# 15-DDR4_DEVICES.net
KiCad netlist of a schematic drawn in Altium Designer
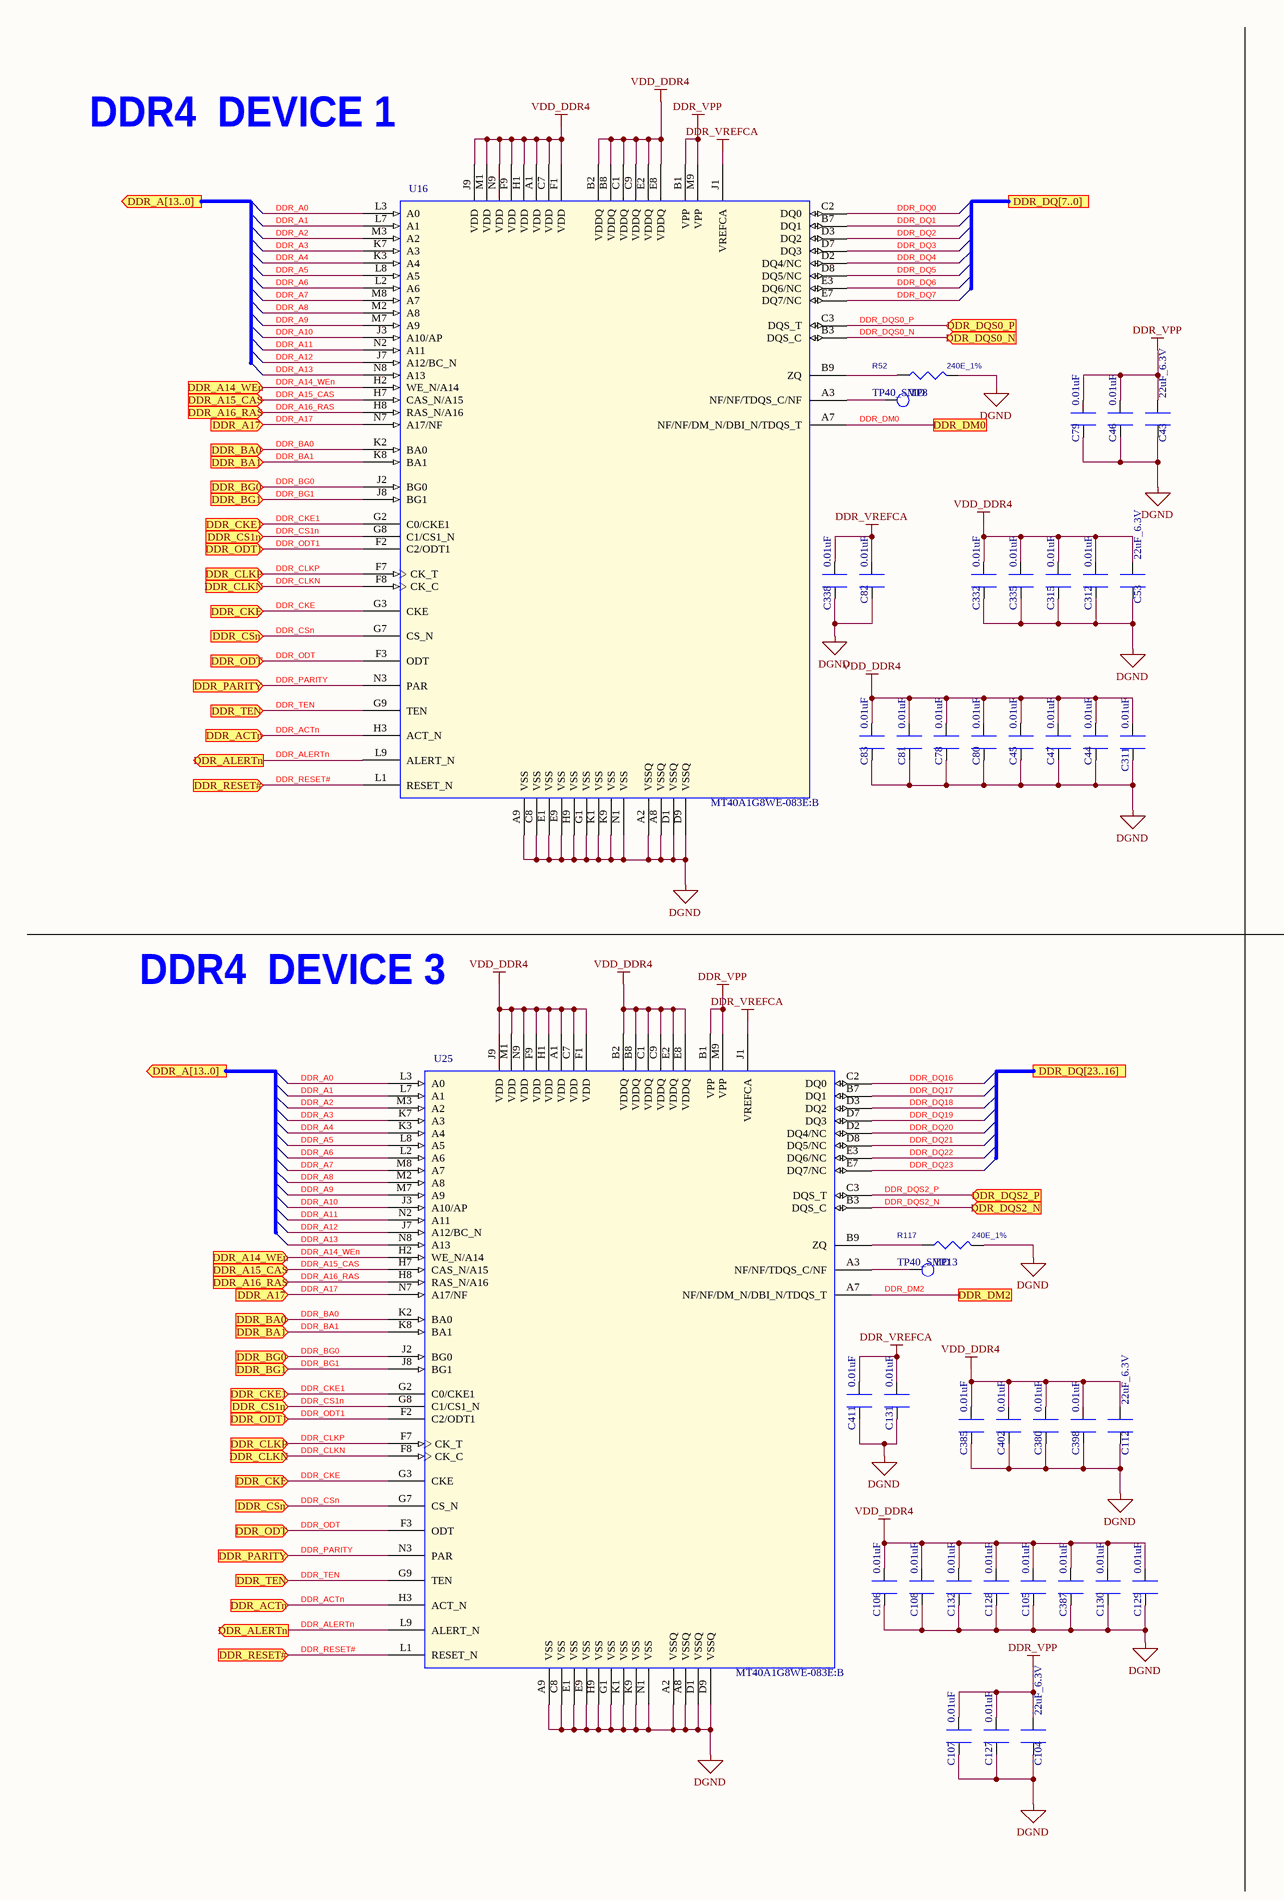
[diagram p0: 15-DDR4 DEVICES.SchDoc, left]
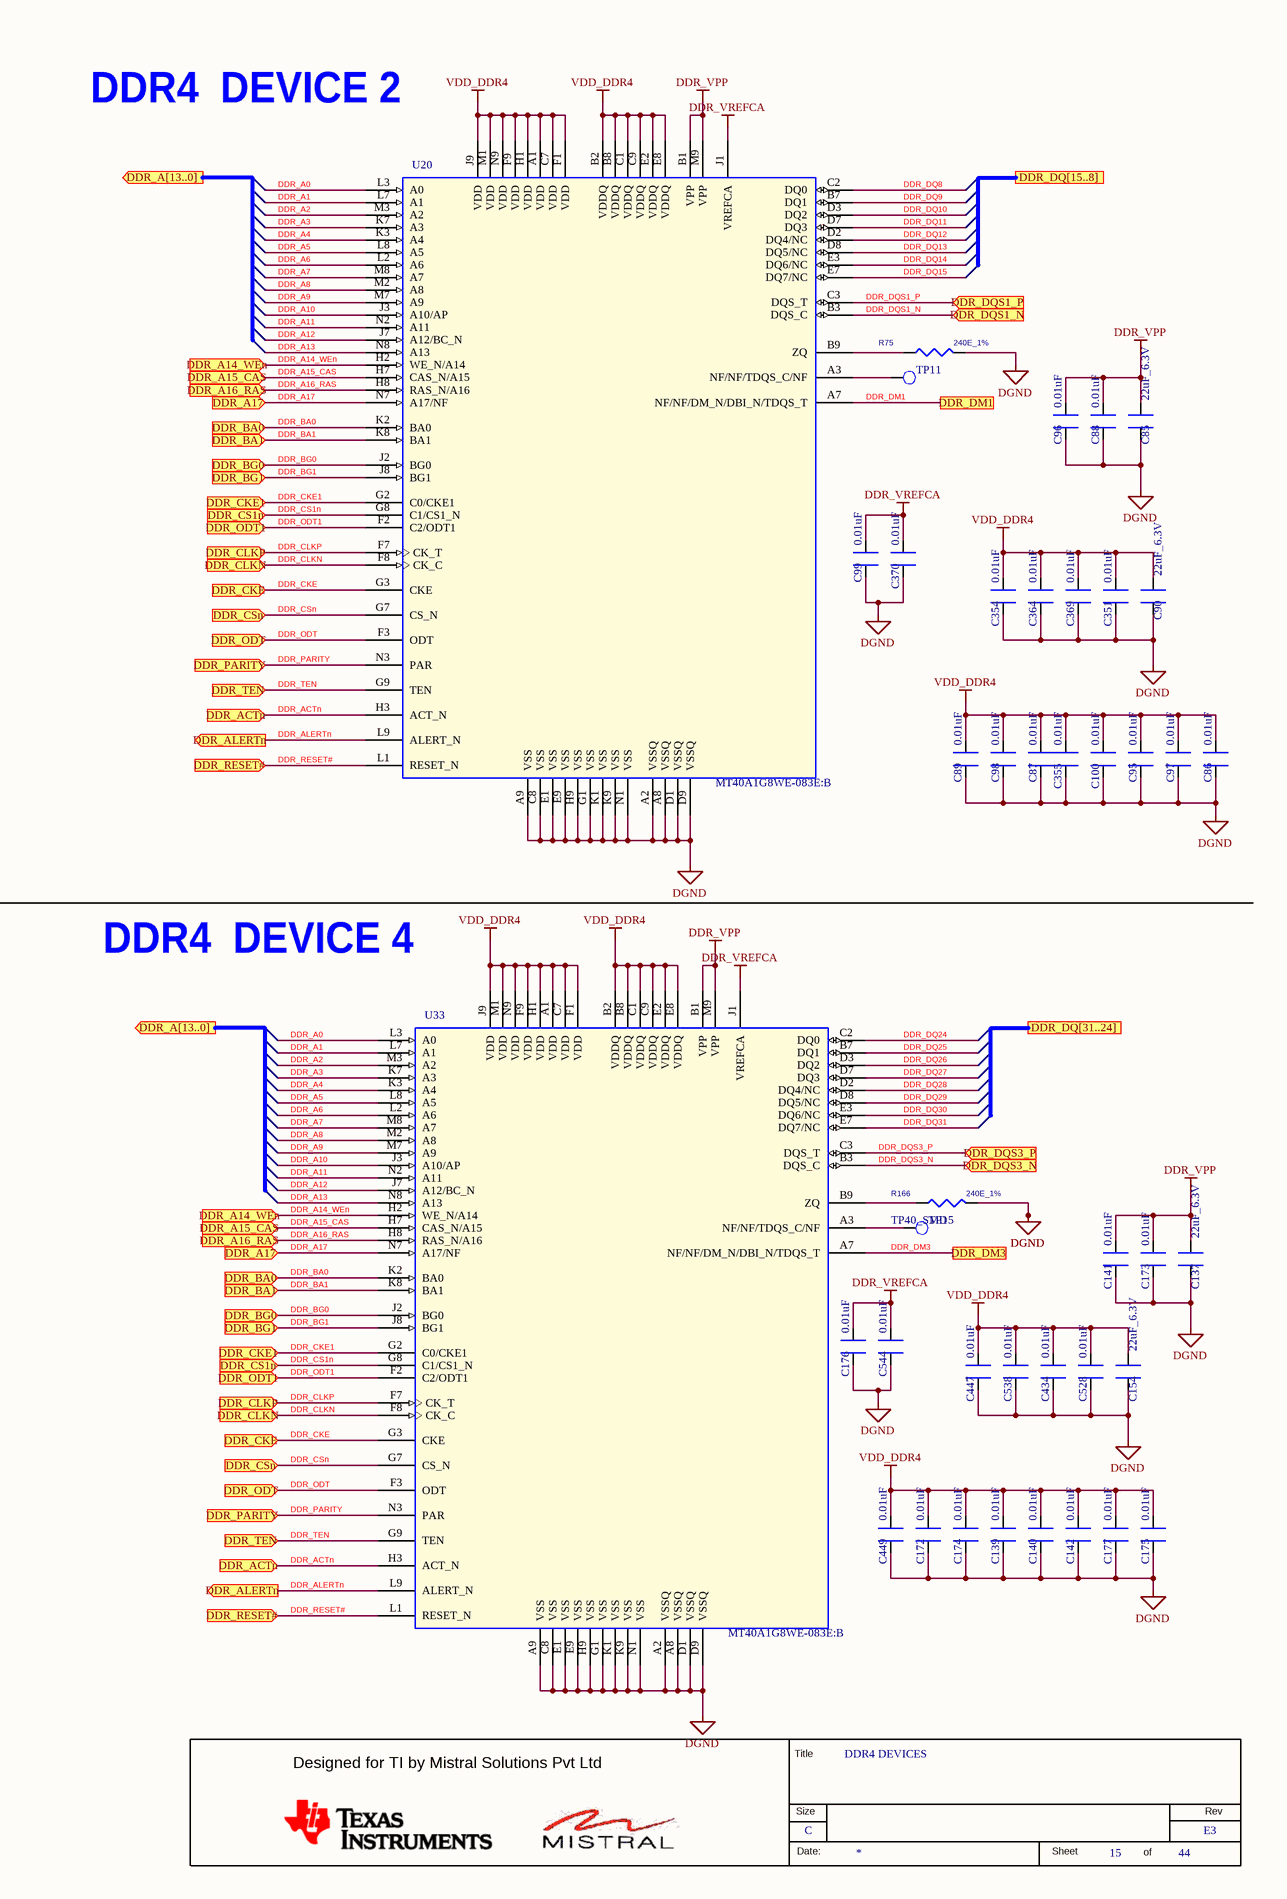
[diagram p1: 15-DDR4 DEVICES.SchDoc, right]

(export (version "E")
  (design (tool "Eeschema 10.0.6"))
  (components
    (comp (ref "C43")
      (value "22uF_6.3V")
      (footprint "TMDX654GPEVM_BRD:CAP0603")
      (description "CAP CERAMIC 22uF 6.3V 20% X5R 0603")
      (fields (field (name "DISTRIBUTOR_PART_NUMBER") "490-7611-2-ND") (field (name "VOLTAGE") "6.3V"))
      (libsource (lib "*") (part "CAP_Dup3"))
    )
    (comp (ref "C44")
      (value "0.01uF")
      (footprint "TMDX654GPEVM_BRD:CAP0201_0-5")
      (description "CAP CERAMIC 0.01uF 25V 10% X5R 0201")
      (fields
        (field (name "MISTRAL PART NO") "120018010007-R")
        (field (name "MFR_PART_NUMBER") "GRM033R61E103KA12J")
      )
      (libsource (lib "*") (part "CAP_Dup3"))
    )
    (comp (ref "C45")
      (value "0.01uF")
      (footprint "TMDX654GPEVM_BRD:CAP0201_0-5")
      (description "CAP CERAMIC 0.01uF 25V 10% X5R 0201")
      (fields
        (field (name "MISTRAL PART NO") "120018010007-R")
        (field (name "MFR_PART_NUMBER") "GRM033R61E103KA12J")
      )
      (libsource (lib "*") (part "CAP_Dup3"))
    )
    (comp (ref "C46")
      (value "0.01uF")
      (footprint "TMDX654GPEVM_BRD:CAP0201_0-5")
      (description "CAP CERAMIC 0.01uF 25V 10% X5R 0201")
      (fields
        (field (name "MISTRAL PART NO") "120018010007-R")
        (field (name "MFR_PART_NUMBER") "GRM033R61E103KA12J")
      )
      (libsource (lib "*") (part "CAP_Dup3"))
    )
    (comp (ref "C47")
      (value "0.01uF")
      (footprint "TMDX654GPEVM_BRD:CAP0201_0-5")
      (description "CAP CERAMIC 0.01uF 25V 10% X5R 0201")
      (fields
        (field (name "MISTRAL PART NO") "120018010007-R")
        (field (name "MFR_PART_NUMBER") "GRM033R61E103KA12J")
      )
      (libsource (lib "*") (part "CAP_Dup3"))
    )
    (comp (ref "C53")
      (value "22uF_6.3V")
      (footprint "TMDX654GPEVM_BRD:CAP0603")
      (description "CAP CERAMIC 22uF 6.3V 20% X5R 0603")
      (fields
        (field (name "MISTRAL PART NO") "120015090007-R")
        (field (name "MFR_PART_NUMBER") "GRM188R60J226MEA0")
      )
      (libsource (lib "*") (part "CAP_Dup3"))
    )
    (comp (ref "C78")
      (value "0.01uF")
      (footprint "TMDX654GPEVM_BRD:CAP0201_0-5")
      (description "CAP CERAMIC 0.01uF 25V 10% X5R 0201")
      (fields
        (field (name "MISTRAL PART NO") "120018010007-R")
        (field (name "MFR_PART_NUMBER") "GRM033R61E103KA12J")
      )
      (libsource (lib "*") (part "CAP_Dup3"))
    )
    (comp (ref "C79")
      (value "0.01uF")
      (footprint "TMDX654GPEVM_BRD:CAP0201_0-5")
      (description "CAP CERAMIC 0.01uF 25V 10% X5R 0201")
      (fields
        (field (name "MISTRAL PART NO") "120018010007-R")
        (field (name "MFR_PART_NUMBER") "GRM033R61E103KA12J")
      )
      (libsource (lib "*") (part "CAP_Dup3"))
    )
    (comp (ref "C80")
      (value "0.01uF")
      (footprint "TMDX654GPEVM_BRD:CAP0201_0-5")
      (description "CAP CERAMIC 0.01uF 25V 10% X5R 0201")
      (fields
        (field (name "MISTRAL PART NO") "120018010007-R")
        (field (name "MFR_PART_NUMBER") "GRM033R61E103KA12J")
      )
      (libsource (lib "*") (part "CAP_Dup3"))
    )
    (comp (ref "C81")
      (value "0.01uF")
      (footprint "TMDX654GPEVM_BRD:CAP0201_0-5")
      (description "CAP CERAMIC 0.01uF 25V 10% X5R 0201")
      (fields
        (field (name "MISTRAL PART NO") "120018010007-R")
        (field (name "MFR_PART_NUMBER") "GRM033R61E103KA12J")
      )
      (libsource (lib "*") (part "CAP_Dup3"))
    )
    (comp (ref "C82")
      (value "0.01uF")
      (footprint "TMDX654GPEVM_BRD:CAP0201_0-5")
      (description "CAP CERAMIC 0.01uF 25V 10% X5R 0201")
      (fields (field (name "DISTRIBUTOR_PART_NUMBER") "GRM033R61E103KA12J-ND") (field (name "VOLTAGE") "25V"))
      (libsource (lib "*") (part "CAP_Dup3"))
    )
    (comp (ref "C83")
      (value "0.01uF")
      (footprint "TMDX654GPEVM_BRD:CAP0201_0-5")
      (description "CAP CERAMIC 0.01uF 25V 10% X5R 0201")
      (fields
        (field (name "MISTRAL PART NO") "120018010007-R")
        (field (name "MFR_PART_NUMBER") "GRM033R61E103KA12J")
      )
      (libsource (lib "*") (part "CAP_Dup3"))
    )
    (comp (ref "C85")
      (value "22uF_6.3V")
      (footprint "TMDX654GPEVM_BRD:CAP0603")
      (description "CAP CERAMIC 22uF 6.3V 20% X5R 0603")
      (fields (field (name "DISTRIBUTOR_PART_NUMBER") "490-7611-2-ND") (field (name "VOLTAGE") "6.3V"))
      (libsource (lib "*") (part "CAP_Dup3"))
    )
    (comp (ref "C86")
      (value "0.01uF")
      (footprint "TMDX654GPEVM_BRD:CAP0201_0-5")
      (description "CAP CERAMIC 0.01uF 25V 10% X5R 0201")
      (fields (field (name "DISTRIBUTOR_PART_NUMBER") "GRM033R61E103KA12J-ND") (field (name "VOLTAGE") "25V"))
      (libsource (lib "*") (part "CAP_Dup3"))
    )
    (comp (ref "C87")
      (value "0.01uF")
      (footprint "TMDX654GPEVM_BRD:CAP0201_0-5")
      (description "CAP CERAMIC 0.01uF 25V 10% X5R 0201")
      (fields
        (field (name "MISTRAL PART NO") "120018010007-R")
        (field (name "MFR_PART_NUMBER") "GRM033R61E103KA12J")
      )
      (libsource (lib "*") (part "CAP_Dup3"))
    )
    (comp (ref "C88")
      (value "0.01uF")
      (footprint "TMDX654GPEVM_BRD:CAP0201_0-5")
      (description "CAP CERAMIC 0.01uF 25V 10% X5R 0201")
      (fields (field (name "DISTRIBUTOR_PART_NUMBER") "GRM033R61E103KA12J-ND") (field (name "VOLTAGE") "25V"))
      (libsource (lib "*") (part "CAP_Dup3"))
    )
    (comp (ref "C89")
      (value "0.01uF")
      (footprint "TMDX654GPEVM_BRD:CAP0201_0-5")
      (description "CAP CERAMIC 0.01uF 25V 10% X5R 0201")
      (fields
        (field (name "MISTRAL PART NO") "120018010007-R")
        (field (name "MFR_PART_NUMBER") "GRM033R61E103KA12J")
      )
      (libsource (lib "*") (part "CAP_Dup3"))
    )
    (comp (ref "C90")
      (value "22uF_6.3V")
      (footprint "TMDX654GPEVM_BRD:CAP0603")
      (description "CAP CERAMIC 22uF 6.3V 20% X5R 0603")
      (fields (field (name "DISTRIBUTOR_PART_NUMBER") "490-7611-2-ND") (field (name "VOLTAGE") "6.3V"))
      (libsource (lib "*") (part "CAP_Dup3"))
    )
    (comp (ref "C95")
      (value "0.01uF")
      (footprint "TMDX654GPEVM_BRD:CAP0201_0-5")
      (description "CAP CERAMIC 0.01uF 25V 10% X5R 0201")
      (fields
        (field (name "MISTRAL PART NO") "120018010007-R")
        (field (name "MFR_PART_NUMBER") "GRM033R61E103KA12J")
      )
      (libsource (lib "*") (part "CAP_Dup3"))
    )
    (comp (ref "C96")
      (value "0.01uF")
      (footprint "TMDX654GPEVM_BRD:CAP0201_0-5")
      (description "CAP CERAMIC 0.01uF 25V 10% X5R 0201")
      (fields (field (name "DISTRIBUTOR_PART_NUMBER") "GRM033R61E103KA12J-ND") (field (name "VOLTAGE") "25V"))
      (libsource (lib "*") (part "CAP_Dup3"))
    )
    (comp (ref "C97")
      (value "0.01uF")
      (footprint "TMDX654GPEVM_BRD:CAP0201_0-5")
      (description "CAP CERAMIC 0.01uF 25V 10% X5R 0201")
      (fields
        (field (name "MISTRAL PART NO") "120018010007-R")
        (field (name "MFR_PART_NUMBER") "GRM033R61E103KA12J")
      )
      (libsource (lib "*") (part "CAP_Dup3"))
    )
    (comp (ref "C98")
      (value "0.01uF")
      (footprint "TMDX654GPEVM_BRD:CAP0201_0-5")
      (description "CAP CERAMIC 0.01uF 25V 10% X5R 0201")
      (fields
        (field (name "MISTRAL PART NO") "120018010007-R")
        (field (name "MFR_PART_NUMBER") "GRM033R61E103KA12J")
      )
      (libsource (lib "*") (part "CAP_Dup3"))
    )
    (comp (ref "C99")
      (value "0.01uF")
      (footprint "TMDX654GPEVM_BRD:CAP0201_0-5")
      (description "CAP CERAMIC 0.01uF 25V 10% X5R 0201")
      (fields (field (name "DISTRIBUTOR_PART_NUMBER") "GRM033R61E103KA12J-ND") (field (name "VOLTAGE") "25V"))
      (libsource (lib "*") (part "CAP_Dup3"))
    )
    (comp (ref "C100")
      (value "0.01uF")
      (footprint "TMDX654GPEVM_BRD:CAP0201_0-5")
      (description "CAP CERAMIC 0.01uF 25V 10% X5R 0201")
      (fields
        (field (name "MISTRAL PART NO") "120018010007-R")
        (field (name "MFR_PART_NUMBER") "GRM033R61E103KA12J")
      )
      (libsource (lib "*") (part "CAP_Dup3"))
    )
    (comp (ref "C104")
      (value "22uF_6.3V")
      (footprint "TMDX654GPEVM_BRD:CAP0603")
      (description "CAP CERAMIC 22uF 6.3V 20% X5R 0603")
      (fields
        (field (name "MISTRAL PART NO") "120015090007-R")
        (field (name "MFR_PART_NUMBER") "GRM188R60J226MEA0")
      )
      (libsource (lib "*") (part "CAP_Dup3"))
    )
    (comp (ref "C105")
      (value "0.01uF")
      (footprint "TMDX654GPEVM_BRD:CAP0201_0-5")
      (description "CAP CERAMIC 0.01uF 25V 10% X5R 0201")
      (fields
        (field (name "MISTRAL PART NO") "120018010007-R")
        (field (name "MFR_PART_NUMBER") "GRM033R61E103KA12J")
      )
      (libsource (lib "*") (part "CAP_Dup3"))
    )
    (comp (ref "C106")
      (value "0.01uF")
      (footprint "TMDX654GPEVM_BRD:CAP0201_0-5")
      (description "CAP CERAMIC 0.01uF 25V 10% X5R 0201")
      (fields
        (field (name "MISTRAL PART NO") "120018010007-R")
        (field (name "MFR_PART_NUMBER") "GRM033R61E103KA12J")
      )
      (libsource (lib "*") (part "CAP_Dup3"))
    )
    (comp (ref "C107")
      (value "0.01uF")
      (footprint "TMDX654GPEVM_BRD:CAP0201_0-5")
      (description "CAP CERAMIC 0.01uF 25V 10% X5R 0201")
      (fields (field (name "DISTRIBUTOR_PART_NUMBER") "GRM033R61E103KA12J-ND") (field (name "VOLTAGE") "25V"))
      (libsource (lib "*") (part "CAP_Dup3"))
    )
    (comp (ref "C108")
      (value "0.01uF")
      (footprint "TMDX654GPEVM_BRD:CAP0201_0-5")
      (description "CAP CERAMIC 0.01uF 25V 10% X5R 0201")
      (fields
        (field (name "MISTRAL PART NO") "120018010007-R")
        (field (name "MFR_PART_NUMBER") "GRM033R61E103KA12J")
      )
      (libsource (lib "*") (part "CAP_Dup3"))
    )
    (comp (ref "C112")
      (value "22uF_6.3V")
      (footprint "TMDX654GPEVM_BRD:CAP0603")
      (description "CAP CERAMIC 22uF 6.3V 20% X5R 0603")
      (fields (field (name "DISTRIBUTOR_PART_NUMBER") "490-7611-2-ND") (field (name "VOLTAGE") "6.3V"))
      (libsource (lib "*") (part "CAP_Dup3"))
    )
    (comp (ref "C127")
      (value "0.01uF")
      (footprint "TMDX654GPEVM_BRD:CAP0201_0-5")
      (description "CAP CERAMIC 0.01uF 25V 10% X5R 0201")
      (fields (field (name "DISTRIBUTOR_PART_NUMBER") "GRM033R61E103KA12J-ND") (field (name "VOLTAGE") "25V"))
      (libsource (lib "*") (part "CAP_Dup3"))
    )
    (comp (ref "C128")
      (value "0.01uF")
      (footprint "TMDX654GPEVM_BRD:CAP0201_0-5")
      (description "CAP CERAMIC 0.01uF 25V 10% X5R 0201")
      (fields
        (field (name "MISTRAL PART NO") "120018010007-R")
        (field (name "MFR_PART_NUMBER") "GRM033R61E103KA12J")
      )
      (libsource (lib "*") (part "CAP_Dup3"))
    )
    (comp (ref "C129")
      (value "0.01uF")
      (footprint "TMDX654GPEVM_BRD:CAP0201_0-5")
      (description "CAP CERAMIC 0.01uF 25V 10% X5R 0201")
      (fields (field (name "DISTRIBUTOR_PART_NUMBER") "GRM033R61E103KA12J-ND") (field (name "VOLTAGE") "25V"))
      (libsource (lib "*") (part "CAP_Dup3"))
    )
    (comp (ref "C130")
      (value "0.01uF")
      (footprint "TMDX654GPEVM_BRD:CAP0201_0-5")
      (description "CAP CERAMIC 0.01uF 25V 10% X5R 0201")
      (fields
        (field (name "MISTRAL PART NO") "120018010007-R")
        (field (name "MFR_PART_NUMBER") "GRM033R61E103KA12J")
      )
      (libsource (lib "*") (part "CAP_Dup3"))
    )
    (comp (ref "C131")
      (value "0.01uF")
      (footprint "TMDX654GPEVM_BRD:CAP0201_0-5")
      (description "CAP CERAMIC 0.01uF 25V 10% X5R 0201")
      (fields (field (name "DISTRIBUTOR_PART_NUMBER") "GRM033R61E103KA12J-ND") (field (name "VOLTAGE") "25V"))
      (libsource (lib "*") (part "CAP_Dup3"))
    )
    (comp (ref "C132")
      (value "0.01uF")
      (footprint "TMDX654GPEVM_BRD:CAP0201_0-5")
      (description "CAP CERAMIC 0.01uF 25V 10% X5R 0201")
      (fields
        (field (name "MISTRAL PART NO") "120018010007-R")
        (field (name "MFR_PART_NUMBER") "GRM033R61E103KA12J")
      )
      (libsource (lib "*") (part "CAP_Dup3"))
    )
    (comp (ref "C137")
      (value "22uF_6.3V")
      (footprint "TMDX654GPEVM_BRD:CAP0603")
      (description "CAP CERAMIC 22uF 6.3V 20% X5R 0603")
      (fields
        (field (name "MISTRAL PART NO") "120015090007-R")
        (field (name "MFR_PART_NUMBER") "GRM188R60J226MEA0")
      )
      (libsource (lib "*") (part "CAP_Dup3"))
    )
    (comp (ref "C139")
      (value "0.01uF")
      (footprint "TMDX654GPEVM_BRD:CAP0201_0-5")
      (description "CAP CERAMIC 0.01uF 25V 10% X5R 0201")
      (fields
        (field (name "MISTRAL PART NO") "120018010007-R")
        (field (name "MFR_PART_NUMBER") "GRM033R61E103KA12J")
      )
      (libsource (lib "*") (part "CAP_Dup3"))
    )
    (comp (ref "C140")
      (value "0.01uF")
      (footprint "TMDX654GPEVM_BRD:CAP0201_0-5")
      (description "CAP CERAMIC 0.01uF 25V 10% X5R 0201")
      (fields
        (field (name "MISTRAL PART NO") "120018010007-R")
        (field (name "MFR_PART_NUMBER") "GRM033R61E103KA12J")
      )
      (libsource (lib "*") (part "CAP_Dup3"))
    )
    (comp (ref "C141")
      (value "0.01uF")
      (footprint "TMDX654GPEVM_BRD:CAP0201_0-5")
      (description "CAP CERAMIC 0.01uF 25V 10% X5R 0201")
      (fields (field (name "DISTRIBUTOR_PART_NUMBER") "GRM033R61E103KA12J-ND") (field (name "VOLTAGE") "25V"))
      (libsource (lib "*") (part "CAP_Dup3"))
    )
    (comp (ref "C142")
      (value "0.01uF")
      (footprint "TMDX654GPEVM_BRD:CAP0201_0-5")
      (description "CAP CERAMIC 0.01uF 25V 10% X5R 0201")
      (fields
        (field (name "MISTRAL PART NO") "120018010007-R")
        (field (name "MFR_PART_NUMBER") "GRM033R61E103KA12J")
      )
      (libsource (lib "*") (part "CAP_Dup3"))
    )
    (comp (ref "C154")
      (value "22uF_6.3V")
      (footprint "TMDX654GPEVM_BRD:CAP0603")
      (description "CAP CERAMIC 22uF 6.3V 20% X5R 0603")
      (fields (field (name "DISTRIBUTOR_PART_NUMBER") "490-7611-2-ND") (field (name "VOLTAGE") "6.3V"))
      (libsource (lib "*") (part "CAP_Dup3"))
    )
    (comp (ref "C172")
      (value "0.01uF")
      (footprint "TMDX654GPEVM_BRD:CAP0201_0-5")
      (description "CAP CERAMIC 0.01uF 25V 10% X5R 0201")
      (fields
        (field (name "MISTRAL PART NO") "120018010007-R")
        (field (name "MFR_PART_NUMBER") "GRM033R61E103KA12J")
      )
      (libsource (lib "*") (part "CAP_Dup3"))
    )
    (comp (ref "C173")
      (value "0.01uF")
      (footprint "TMDX654GPEVM_BRD:CAP0201_0-5")
      (description "CAP CERAMIC 0.01uF 25V 10% X5R 0201")
      (fields (field (name "DISTRIBUTOR_PART_NUMBER") "GRM033R61E103KA12J-ND") (field (name "VOLTAGE") "25V"))
      (libsource (lib "*") (part "CAP_Dup3"))
    )
    (comp (ref "C174")
      (value "0.01uF")
      (footprint "TMDX654GPEVM_BRD:CAP0201_0-5")
      (description "CAP CERAMIC 0.01uF 25V 10% X5R 0201")
      (fields
        (field (name "MISTRAL PART NO") "120018010007-R")
        (field (name "MFR_PART_NUMBER") "GRM033R61E103KA12J")
      )
      (libsource (lib "*") (part "CAP_Dup3"))
    )
    (comp (ref "C175")
      (value "0.01uF")
      (footprint "TMDX654GPEVM_BRD:CAP0201_0-5")
      (description "CAP CERAMIC 0.01uF 25V 10% X5R 0201")
      (fields (field (name "DISTRIBUTOR_PART_NUMBER") "GRM033R61E103KA12J-ND") (field (name "VOLTAGE") "25V"))
      (libsource (lib "*") (part "CAP_Dup3"))
    )
    (comp (ref "C176")
      (value "0.01uF")
      (footprint "TMDX654GPEVM_BRD:CAP0201_0-5")
      (description "CAP CERAMIC 0.01uF 25V 10% X5R 0201")
      (fields (field (name "DISTRIBUTOR_PART_NUMBER") "GRM033R61E103KA12J-ND") (field (name "VOLTAGE") "25V"))
      (libsource (lib "*") (part "CAP_Dup3"))
    )
    (comp (ref "C177")
      (value "0.01uF")
      (footprint "TMDX654GPEVM_BRD:CAP0201_0-5")
      (description "CAP CERAMIC 0.01uF 25V 10% X5R 0201")
      (fields
        (field (name "MISTRAL PART NO") "120018010007-R")
        (field (name "MFR_PART_NUMBER") "GRM033R61E103KA12J")
      )
      (libsource (lib "*") (part "CAP_Dup3"))
    )
    (comp (ref "C311")
      (value "0.01uF")
      (footprint "TMDX654GPEVM_BRD:CAP0201_0-5")
      (description "CAP CERAMIC 0.01uF 25V 10% X5R 0201")
      (fields
        (field (name "MISTRAL PART NO") "120018010007-R")
        (field (name "MFR_PART_NUMBER") "GRM033R61E103KA12J")
      )
      (libsource (lib "*") (part "CAP_Dup3"))
    )
    (comp (ref "C312")
      (value "0.01uF")
      (footprint "TMDX654GPEVM_BRD:CAP0201_0-5")
      (description "CAP CERAMIC 0.01uF 25V 10% X5R 0201")
      (fields (field (name "DISTRIBUTOR_PART_NUMBER") "GRM033R61E103KA12J-ND") (field (name "VOLTAGE") "25V"))
      (libsource (lib "*") (part "CAP_Dup3"))
    )
    (comp (ref "C315")
      (value "0.01uF")
      (footprint "TMDX654GPEVM_BRD:CAP0201_0-5")
      (description "CAP CERAMIC 0.01uF 25V 10% X5R 0201")
      (fields (field (name "DISTRIBUTOR_PART_NUMBER") "GRM033R61E103KA12J-ND") (field (name "VOLTAGE") "25V"))
      (libsource (lib "*") (part "CAP_Dup3"))
    )
    (comp (ref "C332")
      (value "0.01uF")
      (footprint "TMDX654GPEVM_BRD:CAP0201_0-5")
      (description "CAP CERAMIC 0.01uF 25V 10% X5R 0201")
      (fields (field (name "DISTRIBUTOR_PART_NUMBER") "GRM033R61E103KA12J-ND") (field (name "VOLTAGE") "25V"))
      (libsource (lib "*") (part "CAP_Dup3"))
    )
    (comp (ref "C335")
      (value "0.01uF")
      (footprint "TMDX654GPEVM_BRD:CAP0201_0-5")
      (description "CAP CERAMIC 0.01uF 25V 10% X5R 0201")
      (fields (field (name "DISTRIBUTOR_PART_NUMBER") "GRM033R61E103KA12J-ND") (field (name "VOLTAGE") "25V"))
      (libsource (lib "*") (part "CAP_Dup3"))
    )
    (comp (ref "C338")
      (value "0.01uF")
      (footprint "TMDX654GPEVM_BRD:CAP0201_0-5")
      (description "CAP CERAMIC 0.01uF 25V 10% X5R 0201")
      (fields (field (name "DISTRIBUTOR_PART_NUMBER") "GRM033R61E103KA12J-ND") (field (name "VOLTAGE") "25V"))
      (libsource (lib "*") (part "CAP_Dup3"))
    )
    (comp (ref "C351")
      (value "0.01uF")
      (footprint "TMDX654GPEVM_BRD:CAP0201_0-5")
      (description "CAP CERAMIC 0.01uF 25V 10% X5R 0201")
      (fields
        (field (name "MISTRAL PART NO") "120018010007-R")
        (field (name "MFR_PART_NUMBER") "GRM033R61E103KA12J")
      )
      (libsource (lib "*") (part "CAP_Dup3"))
    )
    (comp (ref "C354")
      (value "0.01uF")
      (footprint "TMDX654GPEVM_BRD:CAP0201_0-5")
      (description "CAP CERAMIC 0.01uF 25V 10% X5R 0201")
      (fields
        (field (name "MISTRAL PART NO") "120018010007-R")
        (field (name "MFR_PART_NUMBER") "GRM033R61E103KA12J")
      )
      (libsource (lib "*") (part "CAP_Dup3"))
    )
    (comp (ref "C355")
      (value "0.01uF")
      (footprint "TMDX654GPEVM_BRD:CAP0201_0-5")
      (description "CAP CERAMIC 0.01uF 25V 10% X5R 0201")
      (fields
        (field (name "MISTRAL PART NO") "120018010007-R")
        (field (name "MFR_PART_NUMBER") "GRM033R61E103KA12J")
      )
      (libsource (lib "*") (part "CAP_Dup3"))
    )
    (comp (ref "C364")
      (value "0.01uF")
      (footprint "TMDX654GPEVM_BRD:CAP0201_0-5")
      (description "CAP CERAMIC 0.01uF 25V 10% X5R 0201")
      (fields
        (field (name "MISTRAL PART NO") "120018010007-R")
        (field (name "MFR_PART_NUMBER") "GRM033R61E103KA12J")
      )
      (libsource (lib "*") (part "CAP_Dup3"))
    )
    (comp (ref "C369")
      (value "0.01uF")
      (footprint "TMDX654GPEVM_BRD:CAP0201_0-5")
      (description "CAP CERAMIC 0.01uF 25V 10% X5R 0201")
      (fields
        (field (name "MISTRAL PART NO") "120018010007-R")
        (field (name "MFR_PART_NUMBER") "GRM033R61E103KA12J")
      )
      (libsource (lib "*") (part "CAP_Dup3"))
    )
    (comp (ref "C370")
      (value "0.01uF")
      (footprint "TMDX654GPEVM_BRD:CAP0201_0-5")
      (description "CAP CERAMIC 0.01uF 25V 10% X5R 0201")
      (fields (field (name "DISTRIBUTOR_PART_NUMBER") "GRM033R61E103KA12J-ND") (field (name "VOLTAGE") "25V"))
      (libsource (lib "*") (part "CAP_Dup3"))
    )
    (comp (ref "C380")
      (value "0.01uF")
      (footprint "TMDX654GPEVM_BRD:CAP0201_0-5")
      (description "CAP CERAMIC 0.01uF 25V 10% X5R 0201")
      (fields
        (field (name "MISTRAL PART NO") "120018010007-R")
        (field (name "MFR_PART_NUMBER") "GRM033R61E103KA12J")
      )
      (libsource (lib "*") (part "CAP_Dup3"))
    )
    (comp (ref "C385")
      (value "0.01uF")
      (footprint "TMDX654GPEVM_BRD:CAP0201_0-5")
      (description "CAP CERAMIC 0.01uF 25V 10% X5R 0201")
      (fields
        (field (name "MISTRAL PART NO") "120018010007-R")
        (field (name "MFR_PART_NUMBER") "GRM033R61E103KA12J")
      )
      (libsource (lib "*") (part "CAP_Dup3"))
    )
    (comp (ref "C387")
      (value "0.01uF")
      (footprint "TMDX654GPEVM_BRD:CAP0201_0-5")
      (description "CAP CERAMIC 0.01uF 25V 10% X5R 0201")
      (fields
        (field (name "MISTRAL PART NO") "120018010007-R")
        (field (name "MFR_PART_NUMBER") "GRM033R61E103KA12J")
      )
      (libsource (lib "*") (part "CAP_Dup3"))
    )
    (comp (ref "C398")
      (value "0.01uF")
      (footprint "TMDX654GPEVM_BRD:CAP0201_0-5")
      (description "CAP CERAMIC 0.01uF 25V 10% X5R 0201")
      (fields
        (field (name "MISTRAL PART NO") "120018010007-R")
        (field (name "MFR_PART_NUMBER") "GRM033R61E103KA12J")
      )
      (libsource (lib "*") (part "CAP_Dup3"))
    )
    (comp (ref "C402")
      (value "0.01uF")
      (footprint "TMDX654GPEVM_BRD:CAP0201_0-5")
      (description "CAP CERAMIC 0.01uF 25V 10% X5R 0201")
      (fields
        (field (name "MISTRAL PART NO") "120018010007-R")
        (field (name "MFR_PART_NUMBER") "GRM033R61E103KA12J")
      )
      (libsource (lib "*") (part "CAP_Dup3"))
    )
    (comp (ref "C411")
      (value "0.01uF")
      (footprint "TMDX654GPEVM_BRD:CAP0201_0-5")
      (description "CAP CERAMIC 0.01uF 25V 10% X5R 0201")
      (fields (field (name "DISTRIBUTOR_PART_NUMBER") "GRM033R61E103KA12J-ND") (field (name "VOLTAGE") "25V"))
      (libsource (lib "*") (part "CAP_Dup3"))
    )
    (comp (ref "C434")
      (value "0.01uF")
      (footprint "TMDX654GPEVM_BRD:CAP0201_0-5")
      (description "CAP CERAMIC 0.01uF 25V 10% X5R 0201")
      (fields
        (field (name "MISTRAL PART NO") "120018010007-R")
        (field (name "MFR_PART_NUMBER") "GRM033R61E103KA12J")
      )
      (libsource (lib "*") (part "CAP_Dup3"))
    )
    (comp (ref "C447")
      (value "0.01uF")
      (footprint "TMDX654GPEVM_BRD:CAP0201_0-5")
      (description "CAP CERAMIC 0.01uF 25V 10% X5R 0201")
      (fields
        (field (name "MISTRAL PART NO") "120018010007-R")
        (field (name "MFR_PART_NUMBER") "GRM033R61E103KA12J")
      )
      (libsource (lib "*") (part "CAP_Dup3"))
    )
    (comp (ref "C449")
      (value "0.01uF")
      (footprint "TMDX654GPEVM_BRD:CAP0201_0-5")
      (description "CAP CERAMIC 0.01uF 25V 10% X5R 0201")
      (fields
        (field (name "MISTRAL PART NO") "120018010007-R")
        (field (name "MFR_PART_NUMBER") "GRM033R61E103KA12J")
      )
      (libsource (lib "*") (part "CAP_Dup3"))
    )
    (comp (ref "C528")
      (value "0.01uF")
      (footprint "TMDX654GPEVM_BRD:CAP0201_0-5")
      (description "CAP CERAMIC 0.01uF 25V 10% X5R 0201")
      (fields
        (field (name "MISTRAL PART NO") "120018010007-R")
        (field (name "MFR_PART_NUMBER") "GRM033R61E103KA12J")
      )
      (libsource (lib "*") (part "CAP_Dup3"))
    )
    (comp (ref "C538")
      (value "0.01uF")
      (footprint "TMDX654GPEVM_BRD:CAP0201_0-5")
      (description "CAP CERAMIC 0.01uF 25V 10% X5R 0201")
      (fields
        (field (name "MISTRAL PART NO") "120018010007-R")
        (field (name "MFR_PART_NUMBER") "GRM033R61E103KA12J")
      )
      (libsource (lib "*") (part "CAP_Dup3"))
    )
    (comp (ref "C544")
      (value "0.01uF")
      (footprint "TMDX654GPEVM_BRD:CAP0201_0-5")
      (description "CAP CERAMIC 0.01uF 25V 10% X5R 0201")
      (fields (field (name "DISTRIBUTOR_PART_NUMBER") "GRM033R61E103KA12J-ND") (field (name "VOLTAGE") "25V"))
      (libsource (lib "*") (part "CAP_Dup3"))
    )
    (comp (ref "R52")
      (value "240E_1%")
      (footprint "RES0402")
      (description "RES 240E 1/10W 1% 0402")
      (fields (field (name "DISTRIBUTOR_PART_NUMBER") "P240LCT-ND") (field (name "VOLTAGE") "NA"))
      (libsource (lib "*") (part "RESISTOR_Dup1"))
    )
    (comp (ref "R75")
      (value "240E_1%")
      (footprint "RES0402")
      (description "RES 240E 1/10W 1% 0402")
      (fields (field (name "DISTRIBUTOR_PART_NUMBER") "P240LCT-ND") (field (name "VOLTAGE") "NA"))
      (libsource (lib "*") (part "RESISTOR_Dup1"))
    )
    (comp (ref "R117")
      (value "240E_1%")
      (footprint "RES0402")
      (description "RES 240E 1/10W 1% 0402")
      (fields
        (field (name "MISTRAL PART NO") "110011060017-R")
        (field (name "MFR_PART_NUMBER") "ERJ-2RKF2400X")
      )
      (libsource (lib "*") (part "RESISTOR_Dup1"))
    )
    (comp (ref "R166")
      (value "240E_1%")
      (footprint "RES0402")
      (description "RES 240E 1/10W 1% 0402")
      (fields
        (field (name "MISTRAL PART NO") "110011060017-R")
        (field (name "MFR_PART_NUMBER") "ERJ-2RKF2400X")
      )
      (libsource (lib "*") (part "RESISTOR_Dup1"))
    )
    (comp (ref "TP8")
      (value "TP40_SMD")
      (footprint "TP40_SMD")
      (description "TESTPOINT CIR 40 SMD")
      (fields (field (name "VOLTAGE") "NA") (field (name "MISTRAL PART NO") "130009030933"))
      (libsource (lib "*") (part "TESTPOINT"))
    )
    (comp (ref "TP11")
      (value "TP40_SMD")
      (footprint "TP40_SMD")
      (description "TESTPOINT CIR 40 SMD")
      (fields (field (name "DISTRIBUTOR_PART_NUMBER") "NA") (field (name "MISTRAL PART NO") "130009030933"))
      (libsource (lib "*") (part "TESTPOINT"))
    )
    (comp (ref "TP13")
      (value "TP40_SMD")
      (footprint "TP40_SMD")
      (description "TESTPOINT CIR 40 SMD")
      (fields (field (name "VOLTAGE") "NA") (field (name "MISTRAL PART NO") "130009030933"))
      (libsource (lib "*") (part "TESTPOINT"))
    )
    (comp (ref "TP15")
      (value "TP40_SMD")
      (footprint "TP40_SMD")
      (description "TESTPOINT CIR 40 SMD")
      (fields (field (name "VOLTAGE") "NA") (field (name "MISTRAL PART NO") "130009030933"))
      (libsource (lib "*") (part "TESTPOINT"))
    )
    (comp (ref "U16")
      (value "MT40A1G8WE-083E:B")
      (footprint "FBGA78_31-49_320X480_1-2")
      (description "IC 1G8 DDR4 SDRAM MEMORY FBGA78")
      (fields (field (name "DISTRIBUTOR_PART_NUMBER") "557-1727-1-ND") (field (name "VOLTAGE") "NA"))
      (libsource (lib "*") (part "MT40A1G8WE-083_FBGA78"))
    )
    (comp (ref "U20")
      (value "MT40A1G8WE-083E:B")
      (footprint "FBGA78_31-49_320X480_1-2")
      (description "IC 1G8 DDR4 SDRAM MEMORY FBGA78")
      (fields (field (name "DISTRIBUTOR_PART_NUMBER") "557-1727-1-ND") (field (name "VOLTAGE") "NA"))
      (libsource (lib "*") (part "MT40A1G8WE-083_FBGA78"))
    )
    (comp (ref "U25")
      (value "MT40A1G8WE-083E:B")
      (footprint "FBGA78_31-49_320X480_1-2")
      (description "IC 1G8 DDR4 SDRAM MEMORY FBGA78")
      (fields (field (name "MISTRAL PART NO") "141117080006-R") (field (name "TOLERANCE") "NA"))
      (libsource (lib "*") (part "MT40A1G8WE-083_FBGA78"))
    )
    (comp (ref "U33")
      (value "MT40A1G8WE-083E:B")
      (footprint "FBGA78_31-49_320X480_1-2")
      (description "IC 1G8 DDR4 SDRAM MEMORY FBGA78")
      (fields (field (name "MISTRAL PART NO") "141117080006-R") (field (name "TOLERANCE") "NA"))
      (libsource (lib "*") (part "MT40A1G8WE-083_FBGA78"))
    )
  )
  (nets
    (net (code "1") (name "/DDR_A0") (class "Default")
      (node (ref "U16") (pin "L3") (pinfunction "A0_L3") (pintype "input"))
      (node (ref "U20") (pin "L3") (pinfunction "A0_L3") (pintype "input"))
      (node (ref "U25") (pin "L3") (pinfunction "A0_L3") (pintype "input"))
      (node (ref "U33") (pin "L3") (pinfunction "A0_L3") (pintype "input"))
    )
    (net (code "2") (name "/DDR_A1") (class "Default")
      (node (ref "U16") (pin "L7") (pinfunction "A1_L7") (pintype "input"))
      (node (ref "U20") (pin "L7") (pinfunction "A1_L7") (pintype "input"))
      (node (ref "U25") (pin "L7") (pinfunction "A1_L7") (pintype "input"))
      (node (ref "U33") (pin "L7") (pinfunction "A1_L7") (pintype "input"))
    )
    (net (code "3") (name "/DDR_A2") (class "Default")
      (node (ref "U16") (pin "M3") (pinfunction "A2_M3") (pintype "input"))
      (node (ref "U20") (pin "M3") (pinfunction "A2_M3") (pintype "input"))
      (node (ref "U25") (pin "M3") (pinfunction "A2_M3") (pintype "input"))
      (node (ref "U33") (pin "M3") (pinfunction "A2_M3") (pintype "input"))
    )
    (net (code "4") (name "/DDR_A3") (class "Default")
      (node (ref "U16") (pin "K7") (pinfunction "A3_K7") (pintype "input"))
      (node (ref "U20") (pin "K7") (pinfunction "A3_K7") (pintype "input"))
      (node (ref "U25") (pin "K7") (pinfunction "A3_K7") (pintype "input"))
      (node (ref "U33") (pin "K7") (pinfunction "A3_K7") (pintype "input"))
    )
    (net (code "5") (name "/DDR_A4") (class "Default")
      (node (ref "U16") (pin "K3") (pinfunction "A4_K3") (pintype "input"))
      (node (ref "U20") (pin "K3") (pinfunction "A4_K3") (pintype "input"))
      (node (ref "U25") (pin "K3") (pinfunction "A4_K3") (pintype "input"))
      (node (ref "U33") (pin "K3") (pinfunction "A4_K3") (pintype "input"))
    )
    (net (code "6") (name "/DDR_A5") (class "Default")
      (node (ref "U16") (pin "L8") (pinfunction "A5_L8") (pintype "input"))
      (node (ref "U20") (pin "L8") (pinfunction "A5_L8") (pintype "input"))
      (node (ref "U25") (pin "L8") (pinfunction "A5_L8") (pintype "input"))
      (node (ref "U33") (pin "L8") (pinfunction "A5_L8") (pintype "input"))
    )
    (net (code "7") (name "/DDR_A6") (class "Default")
      (node (ref "U16") (pin "L2") (pinfunction "A6_L2") (pintype "input"))
      (node (ref "U20") (pin "L2") (pinfunction "A6_L2") (pintype "input"))
      (node (ref "U25") (pin "L2") (pinfunction "A6_L2") (pintype "input"))
      (node (ref "U33") (pin "L2") (pinfunction "A6_L2") (pintype "input"))
    )
    (net (code "8") (name "/DDR_A7") (class "Default")
      (node (ref "U16") (pin "M8") (pinfunction "A7_M8") (pintype "input"))
      (node (ref "U20") (pin "M8") (pinfunction "A7_M8") (pintype "input"))
      (node (ref "U25") (pin "M8") (pinfunction "A7_M8") (pintype "input"))
      (node (ref "U33") (pin "M8") (pinfunction "A7_M8") (pintype "input"))
    )
    (net (code "9") (name "/DDR_A8") (class "Default")
      (node (ref "U16") (pin "M2") (pinfunction "A8_M2") (pintype "input"))
      (node (ref "U20") (pin "M2") (pinfunction "A8_M2") (pintype "input"))
      (node (ref "U25") (pin "M2") (pinfunction "A8_M2") (pintype "input"))
      (node (ref "U33") (pin "M2") (pinfunction "A8_M2") (pintype "input"))
    )
    (net (code "10") (name "/DDR_A9") (class "Default")
      (node (ref "U16") (pin "M7") (pinfunction "A9_M7") (pintype "input"))
      (node (ref "U20") (pin "M7") (pinfunction "A9_M7") (pintype "input"))
      (node (ref "U25") (pin "M7") (pinfunction "A9_M7") (pintype "input"))
      (node (ref "U33") (pin "M7") (pinfunction "A9_M7") (pintype "input"))
    )
    (net (code "11") (name "/DDR_A10") (class "Default")
      (node (ref "U16") (pin "J3") (pinfunction "A10/AP_J3") (pintype "input"))
      (node (ref "U20") (pin "J3") (pinfunction "A10/AP_J3") (pintype "input"))
      (node (ref "U25") (pin "J3") (pinfunction "A10/AP_J3") (pintype "input"))
      (node (ref "U33") (pin "J3") (pinfunction "A10/AP_J3") (pintype "input"))
    )
    (net (code "12") (name "/DDR_A11") (class "Default")
      (node (ref "U16") (pin "N2") (pinfunction "A11_N2") (pintype "input"))
      (node (ref "U20") (pin "N2") (pinfunction "A11_N2") (pintype "input"))
      (node (ref "U25") (pin "N2") (pinfunction "A11_N2") (pintype "input"))
      (node (ref "U33") (pin "N2") (pinfunction "A11_N2") (pintype "input"))
    )
    (net (code "13") (name "/DDR_A12") (class "Default")
      (node (ref "U16") (pin "J7") (pinfunction "A12/BC_N_J7") (pintype "input"))
      (node (ref "U20") (pin "J7") (pinfunction "A12/BC_N_J7") (pintype "input"))
      (node (ref "U25") (pin "J7") (pinfunction "A12/BC_N_J7") (pintype "input"))
      (node (ref "U33") (pin "J7") (pinfunction "A12/BC_N_J7") (pintype "input"))
    )
    (net (code "14") (name "/DDR_A13") (class "Default")
      (node (ref "U16") (pin "N8") (pinfunction "A13_N8") (pintype "input"))
      (node (ref "U20") (pin "N8") (pinfunction "A13_N8") (pintype "input"))
      (node (ref "U25") (pin "N8") (pinfunction "A13_N8") (pintype "input"))
      (node (ref "U33") (pin "N8") (pinfunction "A13_N8") (pintype "input"))
    )
    (net (code "15") (name "/DDR_A14_WEn") (class "Default")
      (node (ref "U16") (pin "H2") (pinfunction "WE_N/A14_H2") (pintype "input"))
      (node (ref "U20") (pin "H2") (pinfunction "WE_N/A14_H2") (pintype "input"))
      (node (ref "U25") (pin "H2") (pinfunction "WE_N/A14_H2") (pintype "input"))
      (node (ref "U33") (pin "H2") (pinfunction "WE_N/A14_H2") (pintype "input"))
    )
    (net (code "16") (name "/DDR_A15_CAS") (class "Default")
      (node (ref "U16") (pin "H7") (pinfunction "CAS_N/A15_H7") (pintype "input"))
      (node (ref "U20") (pin "H7") (pinfunction "CAS_N/A15_H7") (pintype "input"))
      (node (ref "U25") (pin "H7") (pinfunction "CAS_N/A15_H7") (pintype "input"))
      (node (ref "U33") (pin "H7") (pinfunction "CAS_N/A15_H7") (pintype "input"))
    )
    (net (code "17") (name "/DDR_A16_RAS") (class "Default")
      (node (ref "U16") (pin "H8") (pinfunction "RAS_N/A16_H8") (pintype "input"))
      (node (ref "U20") (pin "H8") (pinfunction "RAS_N/A16_H8") (pintype "input"))
      (node (ref "U25") (pin "H8") (pinfunction "RAS_N/A16_H8") (pintype "input"))
      (node (ref "U33") (pin "H8") (pinfunction "RAS_N/A16_H8") (pintype "input"))
    )
    (net (code "18") (name "/DDR_A17") (class "Default")
      (node (ref "U16") (pin "N7") (pinfunction "A17/NF_N7") (pintype "input"))
      (node (ref "U20") (pin "N7") (pinfunction "A17/NF_N7") (pintype "input"))
      (node (ref "U25") (pin "N7") (pinfunction "A17/NF_N7") (pintype "input"))
      (node (ref "U33") (pin "N7") (pinfunction "A17/NF_N7") (pintype "input"))
    )
    (net (code "19") (name "/DDR_ACTn") (class "Default")
      (node (ref "U16") (pin "H3") (pinfunction "ACT_N_H3") (pintype "passive"))
      (node (ref "U20") (pin "H3") (pinfunction "ACT_N_H3") (pintype "passive"))
      (node (ref "U25") (pin "H3") (pinfunction "ACT_N_H3") (pintype "passive"))
      (node (ref "U33") (pin "H3") (pinfunction "ACT_N_H3") (pintype "passive"))
    )
    (net (code "20") (name "/DDR_ALERTn") (class "Default")
      (node (ref "U16") (pin "L9") (pinfunction "ALERT_N_L9") (pintype "passive"))
      (node (ref "U20") (pin "L9") (pinfunction "ALERT_N_L9") (pintype "passive"))
      (node (ref "U25") (pin "L9") (pinfunction "ALERT_N_L9") (pintype "passive"))
      (node (ref "U33") (pin "L9") (pinfunction "ALERT_N_L9") (pintype "passive"))
    )
    (net (code "22") (name "/DDR_BA0") (class "Default")
      (node (ref "U16") (pin "K2") (pinfunction "BA0_K2") (pintype "input"))
      (node (ref "U20") (pin "K2") (pinfunction "BA0_K2") (pintype "input"))
      (node (ref "U25") (pin "K2") (pinfunction "BA0_K2") (pintype "input"))
      (node (ref "U33") (pin "K2") (pinfunction "BA0_K2") (pintype "input"))
    )
    (net (code "23") (name "/DDR_BA1") (class "Default")
      (node (ref "U16") (pin "K8") (pinfunction "BA1_K8") (pintype "input"))
      (node (ref "U20") (pin "K8") (pinfunction "BA1_K8") (pintype "input"))
      (node (ref "U25") (pin "K8") (pinfunction "BA1_K8") (pintype "input"))
      (node (ref "U33") (pin "K8") (pinfunction "BA1_K8") (pintype "input"))
    )
    (net (code "24") (name "/DDR_BG0") (class "Default")
      (node (ref "U16") (pin "J2") (pinfunction "BG0_J2") (pintype "input"))
      (node (ref "U20") (pin "J2") (pinfunction "BG0_J2") (pintype "input"))
      (node (ref "U25") (pin "J2") (pinfunction "BG0_J2") (pintype "input"))
      (node (ref "U33") (pin "J2") (pinfunction "BG0_J2") (pintype "input"))
    )
    (net (code "25") (name "/DDR_BG1") (class "Default")
      (node (ref "U16") (pin "J8") (pinfunction "BG1_J8") (pintype "input"))
      (node (ref "U20") (pin "J8") (pinfunction "BG1_J8") (pintype "input"))
      (node (ref "U25") (pin "J8") (pinfunction "BG1_J8") (pintype "input"))
      (node (ref "U33") (pin "J8") (pinfunction "BG1_J8") (pintype "input"))
    )
    (net (code "26") (name "/DDR_CKE") (class "Default")
      (node (ref "U16") (pin "G3") (pinfunction "CKE_G3") (pintype "passive"))
      (node (ref "U20") (pin "G3") (pinfunction "CKE_G3") (pintype "passive"))
      (node (ref "U25") (pin "G3") (pinfunction "CKE_G3") (pintype "passive"))
      (node (ref "U33") (pin "G3") (pinfunction "CKE_G3") (pintype "passive"))
    )
    (net (code "27") (name "/DDR_CKE1") (class "Default")
      (node (ref "U16") (pin "G2") (pinfunction "C0/CKE1_G2") (pintype "passive"))
      (node (ref "U20") (pin "G2") (pinfunction "C0/CKE1_G2") (pintype "passive"))
      (node (ref "U25") (pin "G2") (pinfunction "C0/CKE1_G2") (pintype "passive"))
      (node (ref "U33") (pin "G2") (pinfunction "C0/CKE1_G2") (pintype "passive"))
    )
    (net (code "28") (name "/DDR_CLKN") (class "Default")
      (node (ref "U16") (pin "F8") (pinfunction "CK_C_F8") (pintype "input"))
      (node (ref "U20") (pin "F8") (pinfunction "CK_C_F8") (pintype "input"))
      (node (ref "U25") (pin "F8") (pinfunction "CK_C_F8") (pintype "input"))
      (node (ref "U33") (pin "F8") (pinfunction "CK_C_F8") (pintype "input"))
    )
    (net (code "29") (name "/DDR_CLKP") (class "Default")
      (node (ref "U16") (pin "F7") (pinfunction "CK_T_F7") (pintype "input"))
      (node (ref "U20") (pin "F7") (pinfunction "CK_T_F7") (pintype "input"))
      (node (ref "U25") (pin "F7") (pinfunction "CK_T_F7") (pintype "input"))
      (node (ref "U33") (pin "F7") (pinfunction "CK_T_F7") (pintype "input"))
    )
    (net (code "30") (name "/DDR_CS1n") (class "Default")
      (node (ref "U16") (pin "G8") (pinfunction "C1/CS1_N_G8") (pintype "passive"))
      (node (ref "U20") (pin "G8") (pinfunction "C1/CS1_N_G8") (pintype "passive"))
      (node (ref "U25") (pin "G8") (pinfunction "C1/CS1_N_G8") (pintype "passive"))
      (node (ref "U33") (pin "G8") (pinfunction "C1/CS1_N_G8") (pintype "passive"))
    )
    (net (code "31") (name "/DDR_CSn") (class "Default")
      (node (ref "U16") (pin "G7") (pinfunction "CS_N_G7") (pintype "passive"))
      (node (ref "U20") (pin "G7") (pinfunction "CS_N_G7") (pintype "passive"))
      (node (ref "U25") (pin "G7") (pinfunction "CS_N_G7") (pintype "passive"))
      (node (ref "U33") (pin "G7") (pinfunction "CS_N_G7") (pintype "passive"))
    )
    (net (code "32") (name "/DDR_DM0") (class "Default")
      (node (ref "U16") (pin "A7") (pinfunction "NF/NF/DM_N/DBI_N/TDQS_T_A7") (pintype "passive"))
    )
    (net (code "33") (name "/DDR_DM1") (class "Default")
      (node (ref "U20") (pin "A7") (pinfunction "NF/NF/DM_N/DBI_N/TDQS_T_A7") (pintype "passive"))
    )
    (net (code "34") (name "/DDR_DM2") (class "Default")
      (node (ref "U25") (pin "A7") (pinfunction "NF/NF/DM_N/DBI_N/TDQS_T_A7") (pintype "passive"))
    )
    (net (code "35") (name "/DDR_DM3") (class "Default")
      (node (ref "U33") (pin "A7") (pinfunction "NF/NF/DM_N/DBI_N/TDQS_T_A7") (pintype "passive"))
    )
    (net (code "36") (name "/DDR_DQ0") (class "Default")
      (node (ref "U16") (pin "C2") (pinfunction "DQ0_C2") (pintype "bidirectional"))
    )
    (net (code "37") (name "/DDR_DQ1") (class "Default")
      (node (ref "U16") (pin "B7") (pinfunction "DQ1_B7") (pintype "bidirectional"))
    )
    (net (code "38") (name "/DDR_DQ2") (class "Default")
      (node (ref "U16") (pin "D3") (pinfunction "DQ2_D3") (pintype "bidirectional"))
    )
    (net (code "39") (name "/DDR_DQ3") (class "Default")
      (node (ref "U16") (pin "D7") (pinfunction "DQ3_D7") (pintype "bidirectional"))
    )
    (net (code "40") (name "/DDR_DQ4") (class "Default")
      (node (ref "U16") (pin "D2") (pinfunction "DQ4/NC_D2") (pintype "bidirectional"))
    )
    (net (code "41") (name "/DDR_DQ5") (class "Default")
      (node (ref "U16") (pin "D8") (pinfunction "DQ5/NC_D8") (pintype "bidirectional"))
    )
    (net (code "42") (name "/DDR_DQ6") (class "Default")
      (node (ref "U16") (pin "E3") (pinfunction "DQ6/NC_E3") (pintype "bidirectional"))
    )
    (net (code "43") (name "/DDR_DQ7") (class "Default")
      (node (ref "U16") (pin "E7") (pinfunction "DQ7/NC_E7") (pintype "bidirectional"))
    )
    (net (code "44") (name "/DDR_DQ8") (class "Default")
      (node (ref "U20") (pin "C2") (pinfunction "DQ0_C2") (pintype "bidirectional"))
    )
    (net (code "45") (name "/DDR_DQ9") (class "Default")
      (node (ref "U20") (pin "B7") (pinfunction "DQ1_B7") (pintype "bidirectional"))
    )
    (net (code "46") (name "/DDR_DQ10") (class "Default")
      (node (ref "U20") (pin "D3") (pinfunction "DQ2_D3") (pintype "bidirectional"))
    )
    (net (code "47") (name "/DDR_DQ11") (class "Default")
      (node (ref "U20") (pin "D7") (pinfunction "DQ3_D7") (pintype "bidirectional"))
    )
    (net (code "48") (name "/DDR_DQ12") (class "Default")
      (node (ref "U20") (pin "D2") (pinfunction "DQ4/NC_D2") (pintype "bidirectional"))
    )
    (net (code "49") (name "/DDR_DQ13") (class "Default")
      (node (ref "U20") (pin "D8") (pinfunction "DQ5/NC_D8") (pintype "bidirectional"))
    )
    (net (code "50") (name "/DDR_DQ14") (class "Default")
      (node (ref "U20") (pin "E3") (pinfunction "DQ6/NC_E3") (pintype "bidirectional"))
    )
    (net (code "51") (name "/DDR_DQ15") (class "Default")
      (node (ref "U20") (pin "E7") (pinfunction "DQ7/NC_E7") (pintype "bidirectional"))
    )
    (net (code "52") (name "/DDR_DQ16") (class "Default")
      (node (ref "U25") (pin "C2") (pinfunction "DQ0_C2") (pintype "bidirectional"))
    )
    (net (code "53") (name "/DDR_DQ17") (class "Default")
      (node (ref "U25") (pin "B7") (pinfunction "DQ1_B7") (pintype "bidirectional"))
    )
    (net (code "54") (name "/DDR_DQ18") (class "Default")
      (node (ref "U25") (pin "D3") (pinfunction "DQ2_D3") (pintype "bidirectional"))
    )
    (net (code "55") (name "/DDR_DQ19") (class "Default")
      (node (ref "U25") (pin "D7") (pinfunction "DQ3_D7") (pintype "bidirectional"))
    )
    (net (code "56") (name "/DDR_DQ20") (class "Default")
      (node (ref "U25") (pin "D2") (pinfunction "DQ4/NC_D2") (pintype "bidirectional"))
    )
    (net (code "57") (name "/DDR_DQ21") (class "Default")
      (node (ref "U25") (pin "D8") (pinfunction "DQ5/NC_D8") (pintype "bidirectional"))
    )
    (net (code "58") (name "/DDR_DQ22") (class "Default")
      (node (ref "U25") (pin "E3") (pinfunction "DQ6/NC_E3") (pintype "bidirectional"))
    )
    (net (code "59") (name "/DDR_DQ23") (class "Default")
      (node (ref "U25") (pin "E7") (pinfunction "DQ7/NC_E7") (pintype "bidirectional"))
    )
    (net (code "60") (name "/DDR_DQ24") (class "Default")
      (node (ref "U33") (pin "C2") (pinfunction "DQ0_C2") (pintype "bidirectional"))
    )
    (net (code "61") (name "/DDR_DQ25") (class "Default")
      (node (ref "U33") (pin "B7") (pinfunction "DQ1_B7") (pintype "bidirectional"))
    )
    (net (code "62") (name "/DDR_DQ26") (class "Default")
      (node (ref "U33") (pin "D3") (pinfunction "DQ2_D3") (pintype "bidirectional"))
    )
    (net (code "63") (name "/DDR_DQ27") (class "Default")
      (node (ref "U33") (pin "D7") (pinfunction "DQ3_D7") (pintype "bidirectional"))
    )
    (net (code "64") (name "/DDR_DQ28") (class "Default")
      (node (ref "U33") (pin "D2") (pinfunction "DQ4/NC_D2") (pintype "bidirectional"))
    )
    (net (code "65") (name "/DDR_DQ29") (class "Default")
      (node (ref "U33") (pin "D8") (pinfunction "DQ5/NC_D8") (pintype "bidirectional"))
    )
    (net (code "66") (name "/DDR_DQ30") (class "Default")
      (node (ref "U33") (pin "E3") (pinfunction "DQ6/NC_E3") (pintype "bidirectional"))
    )
    (net (code "67") (name "/DDR_DQ31") (class "Default")
      (node (ref "U33") (pin "E7") (pinfunction "DQ7/NC_E7") (pintype "bidirectional"))
    )
    (net (code "68") (name "/DDR_DQS0_N") (class "Default")
      (node (ref "U16") (pin "B3") (pinfunction "DQS_C_B3") (pintype "bidirectional"))
    )
    (net (code "69") (name "/DDR_DQS0_P") (class "Default")
      (node (ref "U16") (pin "C3") (pinfunction "DQS_T_C3") (pintype "bidirectional"))
    )
    (net (code "70") (name "/DDR_DQS1_N") (class "Default")
      (node (ref "U20") (pin "B3") (pinfunction "DQS_C_B3") (pintype "bidirectional"))
    )
    (net (code "71") (name "/DDR_DQS1_P") (class "Default")
      (node (ref "U20") (pin "C3") (pinfunction "DQS_T_C3") (pintype "bidirectional"))
    )
    (net (code "72") (name "/DDR_DQS2_N") (class "Default")
      (node (ref "U25") (pin "B3") (pinfunction "DQS_C_B3") (pintype "bidirectional"))
    )
    (net (code "73") (name "/DDR_DQS2_P") (class "Default")
      (node (ref "U25") (pin "C3") (pinfunction "DQS_T_C3") (pintype "bidirectional"))
    )
    (net (code "74") (name "/DDR_DQS3_N") (class "Default")
      (node (ref "U33") (pin "B3") (pinfunction "DQS_C_B3") (pintype "bidirectional"))
    )
    (net (code "75") (name "/DDR_DQS3_P") (class "Default")
      (node (ref "U33") (pin "C3") (pinfunction "DQS_T_C3") (pintype "bidirectional"))
    )
    (net (code "80") (name "/DDR_ODT") (class "Default")
      (node (ref "U16") (pin "F3") (pinfunction "ODT_F3") (pintype "passive"))
      (node (ref "U20") (pin "F3") (pinfunction "ODT_F3") (pintype "passive"))
      (node (ref "U25") (pin "F3") (pinfunction "ODT_F3") (pintype "passive"))
      (node (ref "U33") (pin "F3") (pinfunction "ODT_F3") (pintype "passive"))
    )
    (net (code "81") (name "/DDR_ODT1") (class "Default")
      (node (ref "U16") (pin "F2") (pinfunction "C2/ODT1_F2") (pintype "passive"))
      (node (ref "U20") (pin "F2") (pinfunction "C2/ODT1_F2") (pintype "passive"))
      (node (ref "U25") (pin "F2") (pinfunction "C2/ODT1_F2") (pintype "passive"))
      (node (ref "U33") (pin "F2") (pinfunction "C2/ODT1_F2") (pintype "passive"))
    )
    (net (code "82") (name "/DDR_PARITY") (class "Default")
      (node (ref "U16") (pin "N3") (pinfunction "PAR_N3") (pintype "passive"))
      (node (ref "U20") (pin "N3") (pinfunction "PAR_N3") (pintype "passive"))
      (node (ref "U25") (pin "N3") (pinfunction "PAR_N3") (pintype "passive"))
      (node (ref "U33") (pin "N3") (pinfunction "PAR_N3") (pintype "passive"))
    )
    (net (code "83") (name "/DDR_RESET#") (class "Default")
      (node (ref "U16") (pin "L1") (pinfunction "RESET_N_L1") (pintype "passive"))
      (node (ref "U20") (pin "L1") (pinfunction "RESET_N_L1") (pintype "passive"))
      (node (ref "U25") (pin "L1") (pinfunction "RESET_N_L1") (pintype "passive"))
      (node (ref "U33") (pin "L1") (pinfunction "RESET_N_L1") (pintype "passive"))
    )
    (net (code "84") (name "/DDR_TEN") (class "Default")
      (node (ref "U16") (pin "G9") (pinfunction "TEN_G9") (pintype "passive"))
      (node (ref "U20") (pin "G9") (pinfunction "TEN_G9") (pintype "passive"))
      (node (ref "U25") (pin "G9") (pinfunction "TEN_G9") (pintype "passive"))
      (node (ref "U33") (pin "G9") (pinfunction "TEN_G9") (pintype "passive"))
    )
    (net (code "85") (name "DDR_VPP") (class "Default")
      (node (ref "C104") (pin "1") (pinfunction "1_1") (pintype "passive"))
      (node (ref "C107") (pin "1") (pinfunction "1_1") (pintype "passive"))
      (node (ref "C127") (pin "1") (pinfunction "1_1") (pintype "passive"))
      (node (ref "C137") (pin "1") (pinfunction "1_1") (pintype "passive"))
      (node (ref "C141") (pin "1") (pinfunction "1_1") (pintype "passive"))
      (node (ref "C173") (pin "1") (pinfunction "1_1") (pintype "passive"))
      (node (ref "C43") (pin "1") (pinfunction "1_1") (pintype "passive"))
      (node (ref "C46") (pin "1") (pinfunction "1_1") (pintype "passive"))
      (node (ref "C79") (pin "1") (pinfunction "1_1") (pintype "passive"))
      (node (ref "C85") (pin "1") (pinfunction "1_1") (pintype "passive"))
      (node (ref "C88") (pin "1") (pinfunction "1_1") (pintype "passive"))
      (node (ref "C96") (pin "1") (pinfunction "1_1") (pintype "passive"))
      (node (ref "U16") (pin "B1") (pinfunction "VPP_B1") (pintype "power_in"))
      (node (ref "U16") (pin "M9") (pinfunction "VPP_M9") (pintype "power_in"))
      (node (ref "U20") (pin "B1") (pinfunction "VPP_B1") (pintype "power_in"))
      (node (ref "U20") (pin "M9") (pinfunction "VPP_M9") (pintype "power_in"))
      (node (ref "U25") (pin "B1") (pinfunction "VPP_B1") (pintype "power_in"))
      (node (ref "U25") (pin "M9") (pinfunction "VPP_M9") (pintype "power_in"))
      (node (ref "U33") (pin "B1") (pinfunction "VPP_B1") (pintype "power_in"))
      (node (ref "U33") (pin "M9") (pinfunction "VPP_M9") (pintype "power_in"))
    )
    (net (code "86") (name "DDR_VREFCA") (class "Default")
      (node (ref "C131") (pin "1") (pinfunction "1_1") (pintype "passive"))
      (node (ref "C176") (pin "1") (pinfunction "1_1") (pintype "passive"))
      (node (ref "C338") (pin "1") (pinfunction "1_1") (pintype "passive"))
      (node (ref "C370") (pin "1") (pinfunction "1_1") (pintype "passive"))
      (node (ref "C411") (pin "1") (pinfunction "1_1") (pintype "passive"))
      (node (ref "C544") (pin "1") (pinfunction "1_1") (pintype "passive"))
      (node (ref "C82") (pin "1") (pinfunction "1_1") (pintype "passive"))
      (node (ref "C99") (pin "1") (pinfunction "1_1") (pintype "passive"))
      (node (ref "U16") (pin "J1") (pinfunction "VREFCA_J1") (pintype "power_in"))
      (node (ref "U20") (pin "J1") (pinfunction "VREFCA_J1") (pintype "power_in"))
      (node (ref "U25") (pin "J1") (pinfunction "VREFCA_J1") (pintype "power_in"))
      (node (ref "U33") (pin "J1") (pinfunction "VREFCA_J1") (pintype "power_in"))
    )
    (net (code "87") (name "DGND") (class "Default")
      (node (ref "C100") (pin "2") (pinfunction "2_2") (pintype "passive"))
      (node (ref "C104") (pin "2") (pinfunction "2_2") (pintype "passive"))
      (node (ref "C105") (pin "2") (pinfunction "2_2") (pintype "passive"))
      (node (ref "C106") (pin "2") (pinfunction "2_2") (pintype "passive"))
      (node (ref "C107") (pin "2") (pinfunction "2_2") (pintype "passive"))
      (node (ref "C108") (pin "2") (pinfunction "2_2") (pintype "passive"))
      (node (ref "C112") (pin "2") (pinfunction "2_2") (pintype "passive"))
      (node (ref "C127") (pin "2") (pinfunction "2_2") (pintype "passive"))
      (node (ref "C128") (pin "2") (pinfunction "2_2") (pintype "passive"))
      (node (ref "C129") (pin "2") (pinfunction "2_2") (pintype "passive"))
      (node (ref "C130") (pin "2") (pinfunction "2_2") (pintype "passive"))
      (node (ref "C131") (pin "2") (pinfunction "2_2") (pintype "passive"))
      (node (ref "C132") (pin "2") (pinfunction "2_2") (pintype "passive"))
      (node (ref "C137") (pin "2") (pinfunction "2_2") (pintype "passive"))
      (node (ref "C139") (pin "2") (pinfunction "2_2") (pintype "passive"))
      (node (ref "C140") (pin "2") (pinfunction "2_2") (pintype "passive"))
      (node (ref "C141") (pin "2") (pinfunction "2_2") (pintype "passive"))
      (node (ref "C142") (pin "2") (pinfunction "2_2") (pintype "passive"))
      (node (ref "C154") (pin "2") (pinfunction "2_2") (pintype "passive"))
      (node (ref "C172") (pin "2") (pinfunction "2_2") (pintype "passive"))
      (node (ref "C173") (pin "2") (pinfunction "2_2") (pintype "passive"))
      (node (ref "C174") (pin "2") (pinfunction "2_2") (pintype "passive"))
      (node (ref "C175") (pin "2") (pinfunction "2_2") (pintype "passive"))
      (node (ref "C176") (pin "2") (pinfunction "2_2") (pintype "passive"))
      (node (ref "C177") (pin "2") (pinfunction "2_2") (pintype "passive"))
      (node (ref "C311") (pin "2") (pinfunction "2_2") (pintype "passive"))
      (node (ref "C312") (pin "2") (pinfunction "2_2") (pintype "passive"))
      (node (ref "C315") (pin "2") (pinfunction "2_2") (pintype "passive"))
      (node (ref "C332") (pin "2") (pinfunction "2_2") (pintype "passive"))
      (node (ref "C335") (pin "2") (pinfunction "2_2") (pintype "passive"))
      (node (ref "C338") (pin "2") (pinfunction "2_2") (pintype "passive"))
      (node (ref "C351") (pin "2") (pinfunction "2_2") (pintype "passive"))
      (node (ref "C354") (pin "2") (pinfunction "2_2") (pintype "passive"))
      (node (ref "C355") (pin "2") (pinfunction "2_2") (pintype "passive"))
      (node (ref "C364") (pin "2") (pinfunction "2_2") (pintype "passive"))
      (node (ref "C369") (pin "2") (pinfunction "2_2") (pintype "passive"))
      (node (ref "C370") (pin "2") (pinfunction "2_2") (pintype "passive"))
      (node (ref "C380") (pin "2") (pinfunction "2_2") (pintype "passive"))
      (node (ref "C385") (pin "2") (pinfunction "2_2") (pintype "passive"))
      (node (ref "C387") (pin "2") (pinfunction "2_2") (pintype "passive"))
      (node (ref "C398") (pin "2") (pinfunction "2_2") (pintype "passive"))
      (node (ref "C402") (pin "2") (pinfunction "2_2") (pintype "passive"))
      (node (ref "C411") (pin "2") (pinfunction "2_2") (pintype "passive"))
      (node (ref "C43") (pin "2") (pinfunction "2_2") (pintype "passive"))
      (node (ref "C434") (pin "2") (pinfunction "2_2") (pintype "passive"))
      (node (ref "C44") (pin "2") (pinfunction "2_2") (pintype "passive"))
      (node (ref "C447") (pin "2") (pinfunction "2_2") (pintype "passive"))
      (node (ref "C449") (pin "2") (pinfunction "2_2") (pintype "passive"))
      (node (ref "C45") (pin "2") (pinfunction "2_2") (pintype "passive"))
      (node (ref "C46") (pin "2") (pinfunction "2_2") (pintype "passive"))
      (node (ref "C47") (pin "2") (pinfunction "2_2") (pintype "passive"))
      (node (ref "C528") (pin "2") (pinfunction "2_2") (pintype "passive"))
      (node (ref "C53") (pin "2") (pinfunction "2_2") (pintype "passive"))
      (node (ref "C538") (pin "2") (pinfunction "2_2") (pintype "passive"))
      (node (ref "C544") (pin "2") (pinfunction "2_2") (pintype "passive"))
      (node (ref "C78") (pin "2") (pinfunction "2_2") (pintype "passive"))
      (node (ref "C79") (pin "2") (pinfunction "2_2") (pintype "passive"))
      (node (ref "C80") (pin "2") (pinfunction "2_2") (pintype "passive"))
      (node (ref "C81") (pin "2") (pinfunction "2_2") (pintype "passive"))
      (node (ref "C82") (pin "2") (pinfunction "2_2") (pintype "passive"))
      (node (ref "C83") (pin "2") (pinfunction "2_2") (pintype "passive"))
      (node (ref "C85") (pin "2") (pinfunction "2_2") (pintype "passive"))
      (node (ref "C86") (pin "2") (pinfunction "2_2") (pintype "passive"))
      (node (ref "C87") (pin "2") (pinfunction "2_2") (pintype "passive"))
      (node (ref "C88") (pin "2") (pinfunction "2_2") (pintype "passive"))
      (node (ref "C89") (pin "2") (pinfunction "2_2") (pintype "passive"))
      (node (ref "C90") (pin "2") (pinfunction "2_2") (pintype "passive"))
      (node (ref "C95") (pin "2") (pinfunction "2_2") (pintype "passive"))
      (node (ref "C96") (pin "2") (pinfunction "2_2") (pintype "passive"))
      (node (ref "C97") (pin "2") (pinfunction "2_2") (pintype "passive"))
      (node (ref "C98") (pin "2") (pinfunction "2_2") (pintype "passive"))
      (node (ref "C99") (pin "2") (pinfunction "2_2") (pintype "passive"))
      (node (ref "R117") (pin "2") (pinfunction "2_2") (pintype "passive"))
      (node (ref "R166") (pin "2") (pinfunction "2_2") (pintype "passive"))
      (node (ref "R52") (pin "2") (pinfunction "2_2") (pintype "passive"))
      (node (ref "R75") (pin "2") (pinfunction "2_2") (pintype "passive"))
      (node (ref "U16") (pin "A2") (pinfunction "VSSQ_A2") (pintype "power_in"))
      (node (ref "U16") (pin "A8") (pinfunction "VSSQ_A8") (pintype "power_in"))
      (node (ref "U16") (pin "A9") (pinfunction "VSS_A9") (pintype "power_in"))
      (node (ref "U16") (pin "C8") (pinfunction "VSS_C8") (pintype "power_in"))
      (node (ref "U16") (pin "D1") (pinfunction "VSSQ_D1") (pintype "power_in"))
      (node (ref "U16") (pin "D9") (pinfunction "VSSQ_D9") (pintype "power_in"))
      (node (ref "U16") (pin "E1") (pinfunction "VSS_E1") (pintype "power_in"))
      (node (ref "U16") (pin "E9") (pinfunction "VSS_E9") (pintype "power_in"))
      (node (ref "U16") (pin "G1") (pinfunction "VSS_G1") (pintype "power_in"))
      (node (ref "U16") (pin "H9") (pinfunction "VSS_H9") (pintype "power_in"))
      (node (ref "U16") (pin "K1") (pinfunction "VSS_K1") (pintype "power_in"))
      (node (ref "U16") (pin "K9") (pinfunction "VSS_K9") (pintype "power_in"))
      (node (ref "U16") (pin "N1") (pinfunction "VSS_N1") (pintype "power_in"))
      (node (ref "U20") (pin "A2") (pinfunction "VSSQ_A2") (pintype "power_in"))
      (node (ref "U20") (pin "A8") (pinfunction "VSSQ_A8") (pintype "power_in"))
      (node (ref "U20") (pin "A9") (pinfunction "VSS_A9") (pintype "power_in"))
      (node (ref "U20") (pin "C8") (pinfunction "VSS_C8") (pintype "power_in"))
      (node (ref "U20") (pin "D1") (pinfunction "VSSQ_D1") (pintype "power_in"))
      (node (ref "U20") (pin "D9") (pinfunction "VSSQ_D9") (pintype "power_in"))
      (node (ref "U20") (pin "E1") (pinfunction "VSS_E1") (pintype "power_in"))
      (node (ref "U20") (pin "E9") (pinfunction "VSS_E9") (pintype "power_in"))
      (node (ref "U20") (pin "G1") (pinfunction "VSS_G1") (pintype "power_in"))
      (node (ref "U20") (pin "H9") (pinfunction "VSS_H9") (pintype "power_in"))
      (node (ref "U20") (pin "K1") (pinfunction "VSS_K1") (pintype "power_in"))
      (node (ref "U20") (pin "K9") (pinfunction "VSS_K9") (pintype "power_in"))
      (node (ref "U20") (pin "N1") (pinfunction "VSS_N1") (pintype "power_in"))
      (node (ref "U25") (pin "A2") (pinfunction "VSSQ_A2") (pintype "power_in"))
      (node (ref "U25") (pin "A8") (pinfunction "VSSQ_A8") (pintype "power_in"))
      (node (ref "U25") (pin "A9") (pinfunction "VSS_A9") (pintype "power_in"))
      (node (ref "U25") (pin "C8") (pinfunction "VSS_C8") (pintype "power_in"))
      (node (ref "U25") (pin "D1") (pinfunction "VSSQ_D1") (pintype "power_in"))
      (node (ref "U25") (pin "D9") (pinfunction "VSSQ_D9") (pintype "power_in"))
      (node (ref "U25") (pin "E1") (pinfunction "VSS_E1") (pintype "power_in"))
      (node (ref "U25") (pin "E9") (pinfunction "VSS_E9") (pintype "power_in"))
      (node (ref "U25") (pin "G1") (pinfunction "VSS_G1") (pintype "power_in"))
      (node (ref "U25") (pin "H9") (pinfunction "VSS_H9") (pintype "power_in"))
      (node (ref "U25") (pin "K1") (pinfunction "VSS_K1") (pintype "power_in"))
      (node (ref "U25") (pin "K9") (pinfunction "VSS_K9") (pintype "power_in"))
      (node (ref "U25") (pin "N1") (pinfunction "VSS_N1") (pintype "power_in"))
      (node (ref "U33") (pin "A2") (pinfunction "VSSQ_A2") (pintype "power_in"))
      (node (ref "U33") (pin "A8") (pinfunction "VSSQ_A8") (pintype "power_in"))
      (node (ref "U33") (pin "A9") (pinfunction "VSS_A9") (pintype "power_in"))
      (node (ref "U33") (pin "C8") (pinfunction "VSS_C8") (pintype "power_in"))
      (node (ref "U33") (pin "D1") (pinfunction "VSSQ_D1") (pintype "power_in"))
      (node (ref "U33") (pin "D9") (pinfunction "VSSQ_D9") (pintype "power_in"))
      (node (ref "U33") (pin "E1") (pinfunction "VSS_E1") (pintype "power_in"))
      (node (ref "U33") (pin "E9") (pinfunction "VSS_E9") (pintype "power_in"))
      (node (ref "U33") (pin "G1") (pinfunction "VSS_G1") (pintype "power_in"))
      (node (ref "U33") (pin "H9") (pinfunction "VSS_H9") (pintype "power_in"))
      (node (ref "U33") (pin "K1") (pinfunction "VSS_K1") (pintype "power_in"))
      (node (ref "U33") (pin "K9") (pinfunction "VSS_K9") (pintype "power_in"))
      (node (ref "U33") (pin "N1") (pinfunction "VSS_N1") (pintype "power_in"))
    )
    (net (code "88") (name "Net-(TP8-TP)") (class "Default")
      (node (ref "TP8") (pin "1") (pinfunction "TP_1") (pintype "passive"))
      (node (ref "U16") (pin "A3") (pinfunction "NF/NF/TDQS_C/NF_A3") (pintype "passive"))
    )
    (net (code "89") (name "Net-(TP11-TP)") (class "Default")
      (node (ref "TP11") (pin "1") (pinfunction "TP_1") (pintype "passive"))
      (node (ref "U20") (pin "A3") (pinfunction "NF/NF/TDQS_C/NF_A3") (pintype "passive"))
    )
    (net (code "90") (name "Net-(TP13-TP)") (class "Default")
      (node (ref "TP13") (pin "1") (pinfunction "TP_1") (pintype "passive"))
      (node (ref "U25") (pin "A3") (pinfunction "NF/NF/TDQS_C/NF_A3") (pintype "passive"))
    )
    (net (code "91") (name "Net-(TP15-TP)") (class "Default")
      (node (ref "TP15") (pin "1") (pinfunction "TP_1") (pintype "passive"))
      (node (ref "U33") (pin "A3") (pinfunction "NF/NF/TDQS_C/NF_A3") (pintype "passive"))
    )
    (net (code "92") (name "Net-(U16-ZQ)") (class "Default")
      (node (ref "R52") (pin "1") (pinfunction "1_1") (pintype "passive"))
      (node (ref "U16") (pin "B9") (pinfunction "ZQ_B9") (pintype "passive"))
    )
    (net (code "93") (name "Net-(U20-ZQ)") (class "Default")
      (node (ref "R75") (pin "1") (pinfunction "1_1") (pintype "passive"))
      (node (ref "U20") (pin "B9") (pinfunction "ZQ_B9") (pintype "passive"))
    )
    (net (code "94") (name "Net-(U25-ZQ)") (class "Default")
      (node (ref "R117") (pin "1") (pinfunction "1_1") (pintype "passive"))
      (node (ref "U25") (pin "B9") (pinfunction "ZQ_B9") (pintype "passive"))
    )
    (net (code "95") (name "Net-(U33-ZQ)") (class "Default")
      (node (ref "R166") (pin "1") (pinfunction "1_1") (pintype "passive"))
      (node (ref "U33") (pin "B9") (pinfunction "ZQ_B9") (pintype "passive"))
    )
    (net (code "96") (name "VDD_DDR4") (class "Default")
      (node (ref "C100") (pin "1") (pinfunction "1_1") (pintype "passive"))
      (node (ref "C105") (pin "1") (pinfunction "1_1") (pintype "passive"))
      (node (ref "C106") (pin "1") (pinfunction "1_1") (pintype "passive"))
      (node (ref "C108") (pin "1") (pinfunction "1_1") (pintype "passive"))
      (node (ref "C112") (pin "1") (pinfunction "1_1") (pintype "passive"))
      (node (ref "C128") (pin "1") (pinfunction "1_1") (pintype "passive"))
      (node (ref "C129") (pin "1") (pinfunction "1_1") (pintype "passive"))
      (node (ref "C130") (pin "1") (pinfunction "1_1") (pintype "passive"))
      (node (ref "C132") (pin "1") (pinfunction "1_1") (pintype "passive"))
      (node (ref "C139") (pin "1") (pinfunction "1_1") (pintype "passive"))
      (node (ref "C140") (pin "1") (pinfunction "1_1") (pintype "passive"))
      (node (ref "C142") (pin "1") (pinfunction "1_1") (pintype "passive"))
      (node (ref "C154") (pin "1") (pinfunction "1_1") (pintype "passive"))
      (node (ref "C172") (pin "1") (pinfunction "1_1") (pintype "passive"))
      (node (ref "C174") (pin "1") (pinfunction "1_1") (pintype "passive"))
      (node (ref "C175") (pin "1") (pinfunction "1_1") (pintype "passive"))
      (node (ref "C177") (pin "1") (pinfunction "1_1") (pintype "passive"))
      (node (ref "C311") (pin "1") (pinfunction "1_1") (pintype "passive"))
      (node (ref "C312") (pin "1") (pinfunction "1_1") (pintype "passive"))
      (node (ref "C315") (pin "1") (pinfunction "1_1") (pintype "passive"))
      (node (ref "C332") (pin "1") (pinfunction "1_1") (pintype "passive"))
      (node (ref "C335") (pin "1") (pinfunction "1_1") (pintype "passive"))
      (node (ref "C351") (pin "1") (pinfunction "1_1") (pintype "passive"))
      (node (ref "C354") (pin "1") (pinfunction "1_1") (pintype "passive"))
      (node (ref "C355") (pin "1") (pinfunction "1_1") (pintype "passive"))
      (node (ref "C364") (pin "1") (pinfunction "1_1") (pintype "passive"))
      (node (ref "C369") (pin "1") (pinfunction "1_1") (pintype "passive"))
      (node (ref "C380") (pin "1") (pinfunction "1_1") (pintype "passive"))
      (node (ref "C385") (pin "1") (pinfunction "1_1") (pintype "passive"))
      (node (ref "C387") (pin "1") (pinfunction "1_1") (pintype "passive"))
      (node (ref "C398") (pin "1") (pinfunction "1_1") (pintype "passive"))
      (node (ref "C402") (pin "1") (pinfunction "1_1") (pintype "passive"))
      (node (ref "C434") (pin "1") (pinfunction "1_1") (pintype "passive"))
      (node (ref "C44") (pin "1") (pinfunction "1_1") (pintype "passive"))
      (node (ref "C447") (pin "1") (pinfunction "1_1") (pintype "passive"))
      (node (ref "C449") (pin "1") (pinfunction "1_1") (pintype "passive"))
      (node (ref "C45") (pin "1") (pinfunction "1_1") (pintype "passive"))
      (node (ref "C47") (pin "1") (pinfunction "1_1") (pintype "passive"))
      (node (ref "C528") (pin "1") (pinfunction "1_1") (pintype "passive"))
      (node (ref "C53") (pin "1") (pinfunction "1_1") (pintype "passive"))
      (node (ref "C538") (pin "1") (pinfunction "1_1") (pintype "passive"))
      (node (ref "C78") (pin "1") (pinfunction "1_1") (pintype "passive"))
      (node (ref "C80") (pin "1") (pinfunction "1_1") (pintype "passive"))
      (node (ref "C81") (pin "1") (pinfunction "1_1") (pintype "passive"))
      (node (ref "C83") (pin "1") (pinfunction "1_1") (pintype "passive"))
      (node (ref "C86") (pin "1") (pinfunction "1_1") (pintype "passive"))
      (node (ref "C87") (pin "1") (pinfunction "1_1") (pintype "passive"))
      (node (ref "C89") (pin "1") (pinfunction "1_1") (pintype "passive"))
      (node (ref "C90") (pin "1") (pinfunction "1_1") (pintype "passive"))
      (node (ref "C95") (pin "1") (pinfunction "1_1") (pintype "passive"))
      (node (ref "C97") (pin "1") (pinfunction "1_1") (pintype "passive"))
      (node (ref "C98") (pin "1") (pinfunction "1_1") (pintype "passive"))
      (node (ref "U16") (pin "A1") (pinfunction "VDD_A1") (pintype "power_in"))
      (node (ref "U16") (pin "B2") (pinfunction "VDDQ_B2") (pintype "power_in"))
      (node (ref "U16") (pin "B8") (pinfunction "VDDQ_B8") (pintype "power_in"))
      (node (ref "U16") (pin "C1") (pinfunction "VDDQ_C1") (pintype "power_in"))
      (node (ref "U16") (pin "C7") (pinfunction "VDD_C7") (pintype "power_in"))
      (node (ref "U16") (pin "C9") (pinfunction "VDDQ_C9") (pintype "power_in"))
      (node (ref "U16") (pin "E2") (pinfunction "VDDQ_E2") (pintype "power_in"))
      (node (ref "U16") (pin "E8") (pinfunction "VDDQ_E8") (pintype "power_in"))
      (node (ref "U16") (pin "F1") (pinfunction "VDD_F1") (pintype "power_in"))
      (node (ref "U16") (pin "F9") (pinfunction "VDD_F9") (pintype "power_in"))
      (node (ref "U16") (pin "H1") (pinfunction "VDD_H1") (pintype "power_in"))
      (node (ref "U16") (pin "J9") (pinfunction "VDD_J9") (pintype "power_in"))
      (node (ref "U16") (pin "M1") (pinfunction "VDD_M1") (pintype "power_in"))
      (node (ref "U16") (pin "N9") (pinfunction "VDD_N9") (pintype "power_in"))
      (node (ref "U20") (pin "A1") (pinfunction "VDD_A1") (pintype "power_in"))
      (node (ref "U20") (pin "B2") (pinfunction "VDDQ_B2") (pintype "power_in"))
      (node (ref "U20") (pin "B8") (pinfunction "VDDQ_B8") (pintype "power_in"))
      (node (ref "U20") (pin "C1") (pinfunction "VDDQ_C1") (pintype "power_in"))
      (node (ref "U20") (pin "C7") (pinfunction "VDD_C7") (pintype "power_in"))
      (node (ref "U20") (pin "C9") (pinfunction "VDDQ_C9") (pintype "power_in"))
      (node (ref "U20") (pin "E2") (pinfunction "VDDQ_E2") (pintype "power_in"))
      (node (ref "U20") (pin "E8") (pinfunction "VDDQ_E8") (pintype "power_in"))
      (node (ref "U20") (pin "F1") (pinfunction "VDD_F1") (pintype "power_in"))
      (node (ref "U20") (pin "F9") (pinfunction "VDD_F9") (pintype "power_in"))
      (node (ref "U20") (pin "H1") (pinfunction "VDD_H1") (pintype "power_in"))
      (node (ref "U20") (pin "J9") (pinfunction "VDD_J9") (pintype "power_in"))
      (node (ref "U20") (pin "M1") (pinfunction "VDD_M1") (pintype "power_in"))
      (node (ref "U20") (pin "N9") (pinfunction "VDD_N9") (pintype "power_in"))
      (node (ref "U25") (pin "A1") (pinfunction "VDD_A1") (pintype "power_in"))
      (node (ref "U25") (pin "B2") (pinfunction "VDDQ_B2") (pintype "power_in"))
      (node (ref "U25") (pin "B8") (pinfunction "VDDQ_B8") (pintype "power_in"))
      (node (ref "U25") (pin "C1") (pinfunction "VDDQ_C1") (pintype "power_in"))
      (node (ref "U25") (pin "C7") (pinfunction "VDD_C7") (pintype "power_in"))
      (node (ref "U25") (pin "C9") (pinfunction "VDDQ_C9") (pintype "power_in"))
      (node (ref "U25") (pin "E2") (pinfunction "VDDQ_E2") (pintype "power_in"))
      (node (ref "U25") (pin "E8") (pinfunction "VDDQ_E8") (pintype "power_in"))
      (node (ref "U25") (pin "F1") (pinfunction "VDD_F1") (pintype "power_in"))
      (node (ref "U25") (pin "F9") (pinfunction "VDD_F9") (pintype "power_in"))
      (node (ref "U25") (pin "H1") (pinfunction "VDD_H1") (pintype "power_in"))
      (node (ref "U25") (pin "J9") (pinfunction "VDD_J9") (pintype "power_in"))
      (node (ref "U25") (pin "M1") (pinfunction "VDD_M1") (pintype "power_in"))
      (node (ref "U25") (pin "N9") (pinfunction "VDD_N9") (pintype "power_in"))
      (node (ref "U33") (pin "A1") (pinfunction "VDD_A1") (pintype "power_in"))
      (node (ref "U33") (pin "B2") (pinfunction "VDDQ_B2") (pintype "power_in"))
      (node (ref "U33") (pin "B8") (pinfunction "VDDQ_B8") (pintype "power_in"))
      (node (ref "U33") (pin "C1") (pinfunction "VDDQ_C1") (pintype "power_in"))
      (node (ref "U33") (pin "C7") (pinfunction "VDD_C7") (pintype "power_in"))
      (node (ref "U33") (pin "C9") (pinfunction "VDDQ_C9") (pintype "power_in"))
      (node (ref "U33") (pin "E2") (pinfunction "VDDQ_E2") (pintype "power_in"))
      (node (ref "U33") (pin "E8") (pinfunction "VDDQ_E8") (pintype "power_in"))
      (node (ref "U33") (pin "F1") (pinfunction "VDD_F1") (pintype "power_in"))
      (node (ref "U33") (pin "F9") (pinfunction "VDD_F9") (pintype "power_in"))
      (node (ref "U33") (pin "H1") (pinfunction "VDD_H1") (pintype "power_in"))
      (node (ref "U33") (pin "J9") (pinfunction "VDD_J9") (pintype "power_in"))
      (node (ref "U33") (pin "M1") (pinfunction "VDD_M1") (pintype "power_in"))
      (node (ref "U33") (pin "N9") (pinfunction "VDD_N9") (pintype "power_in"))
    )
  )
)
